# XMICRO-6502_V2_3.net
KiCad netlist of a schematic drawn in EAGLE
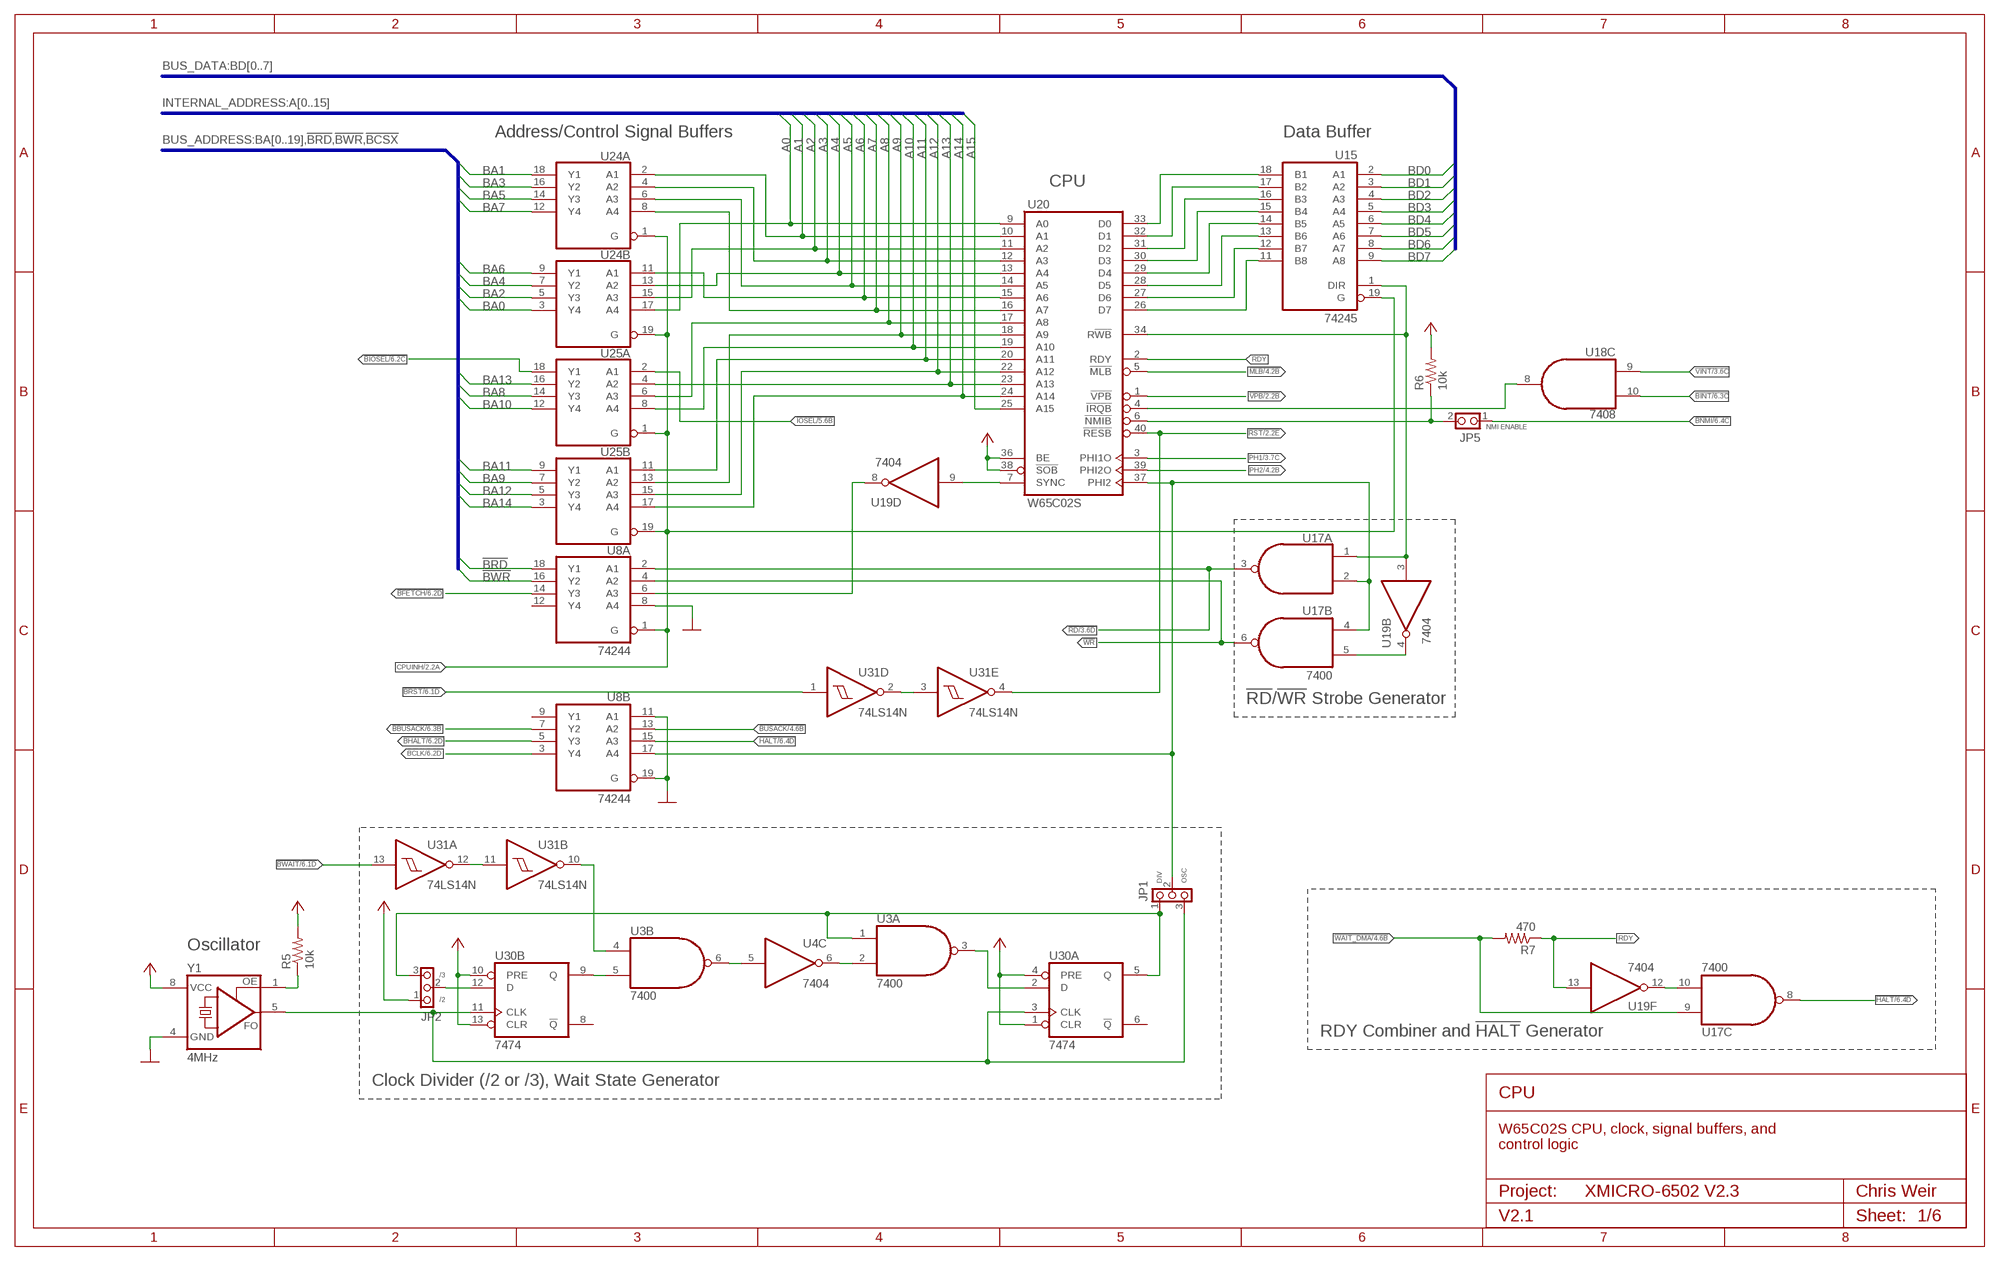
[diagram p0: schematic, sheet 1]
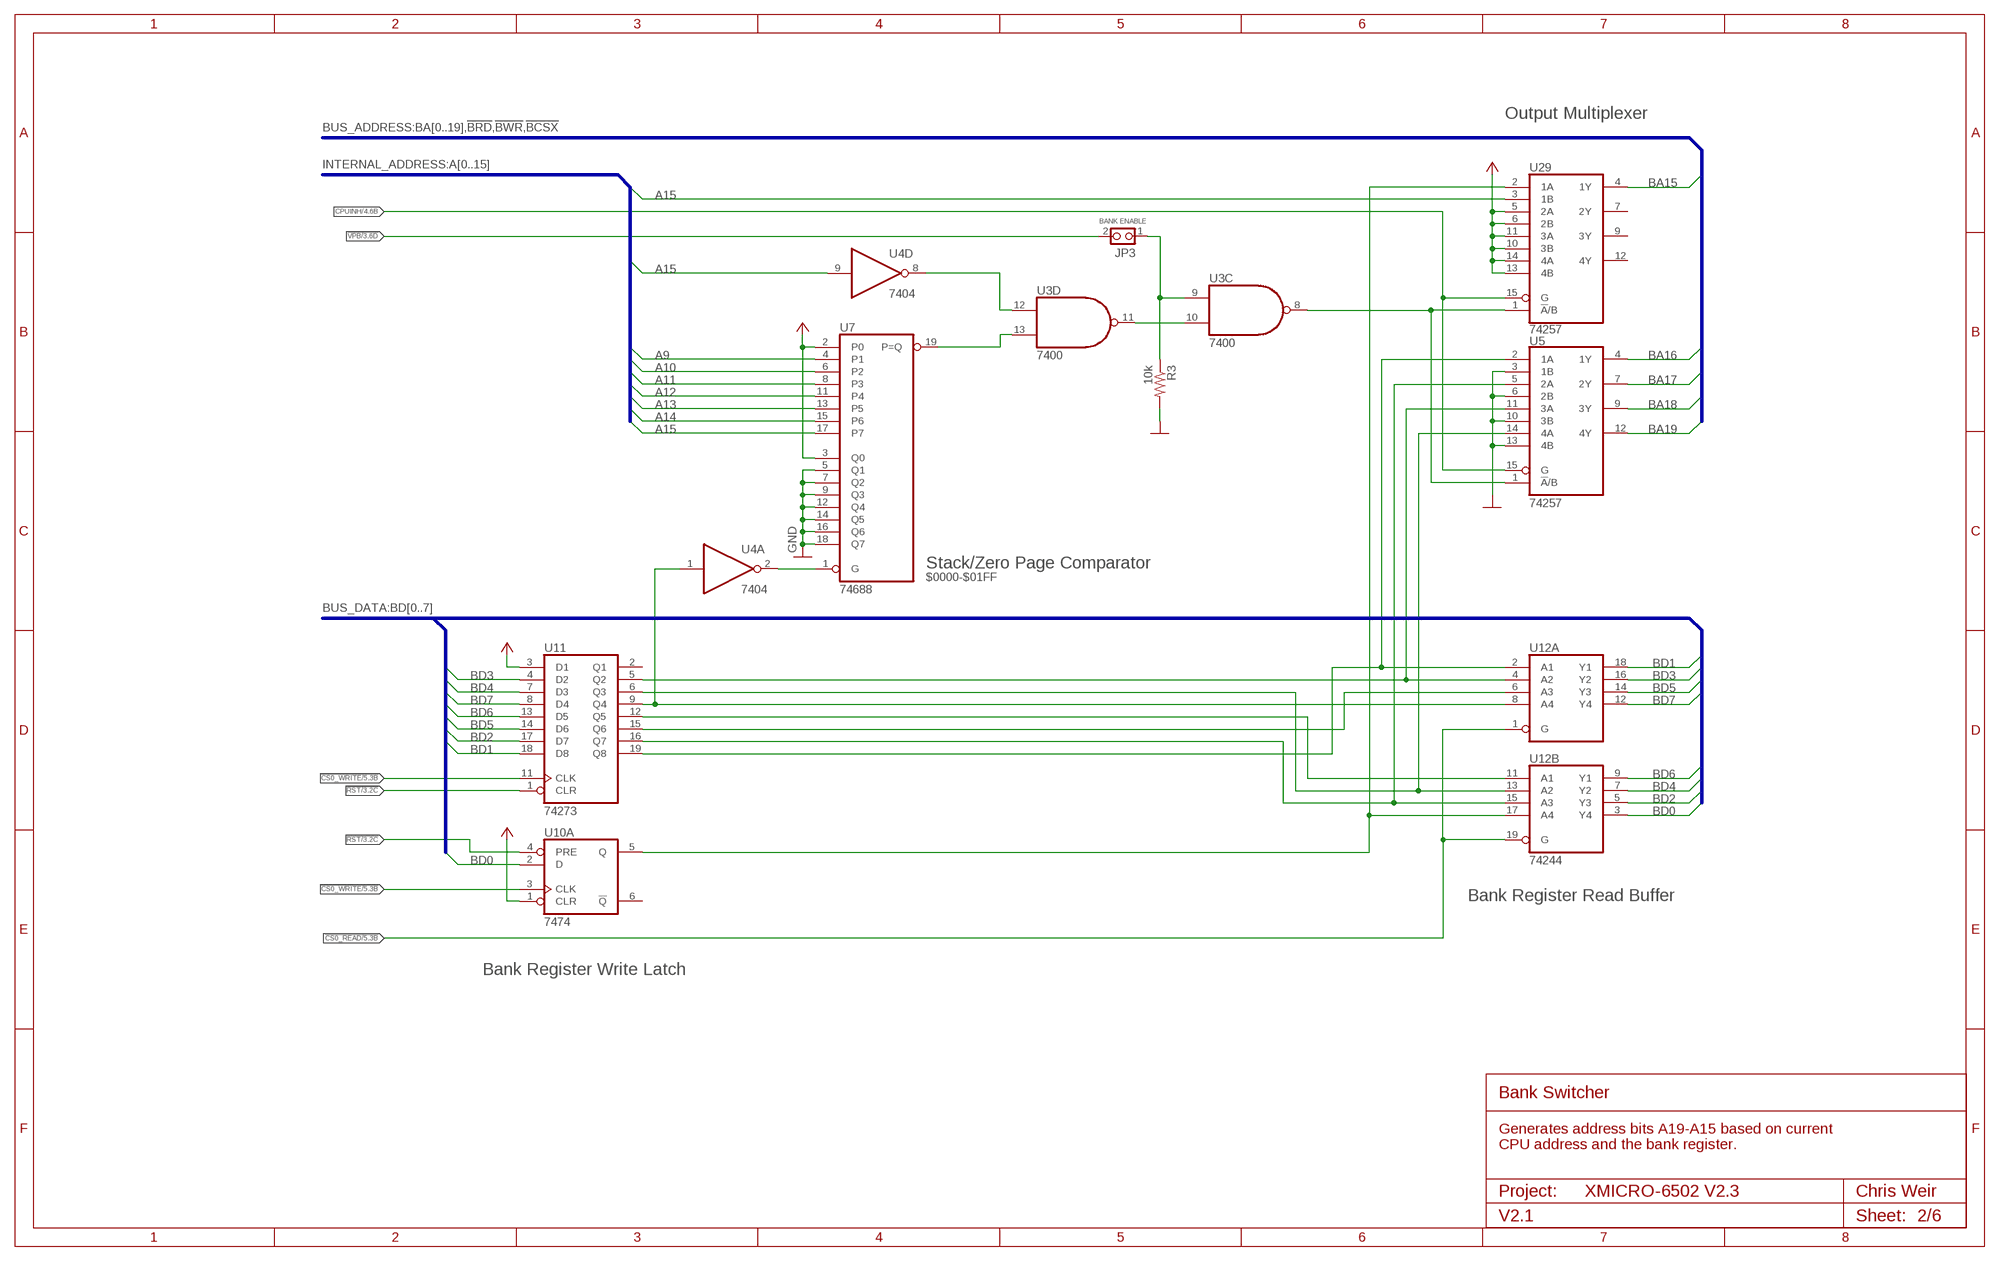
[diagram p1: schematic, sheet 2]
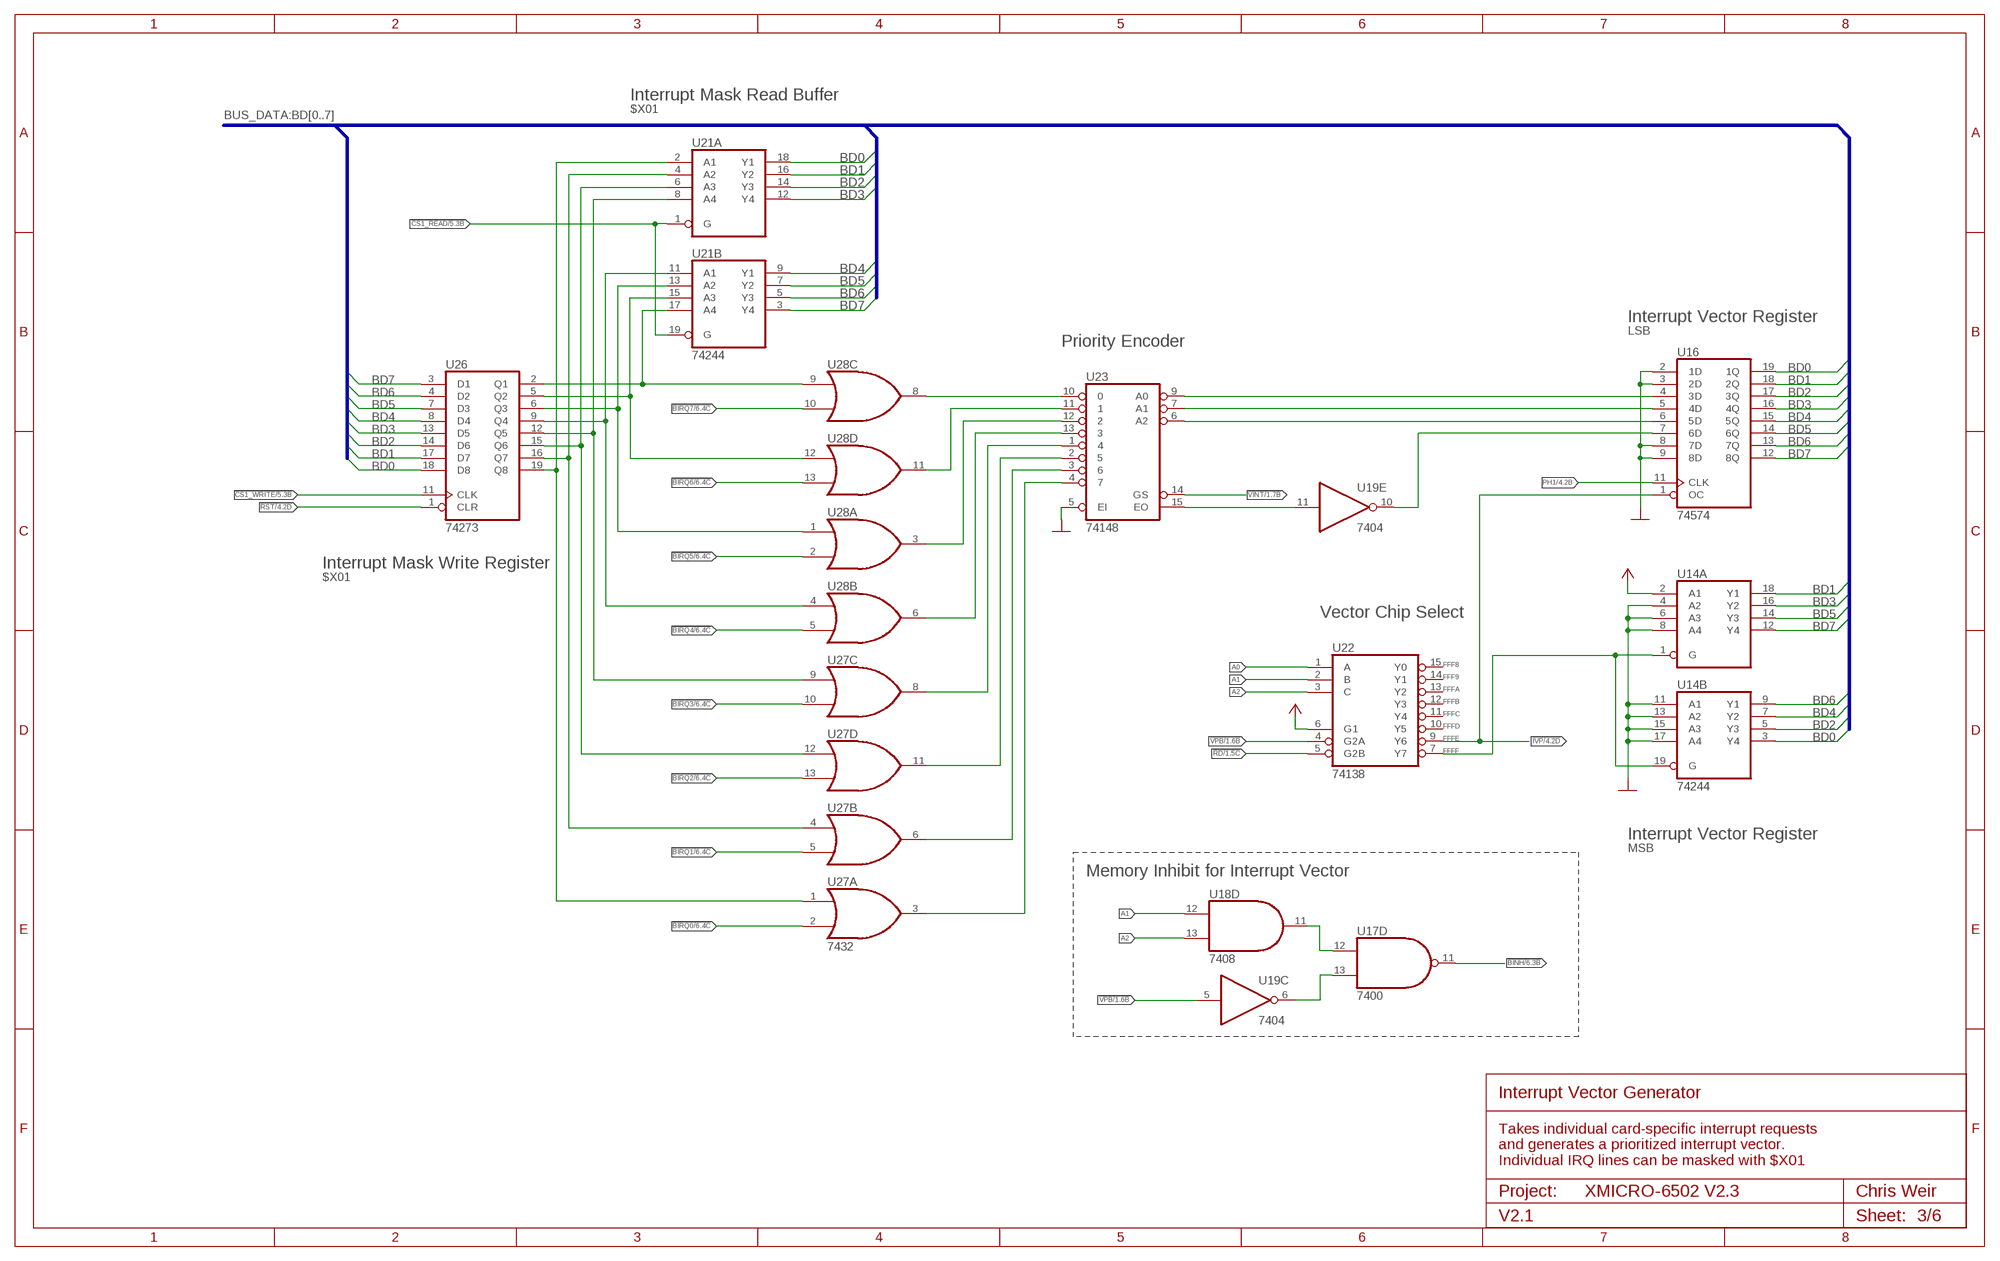
[diagram p2: schematic, sheet 3]
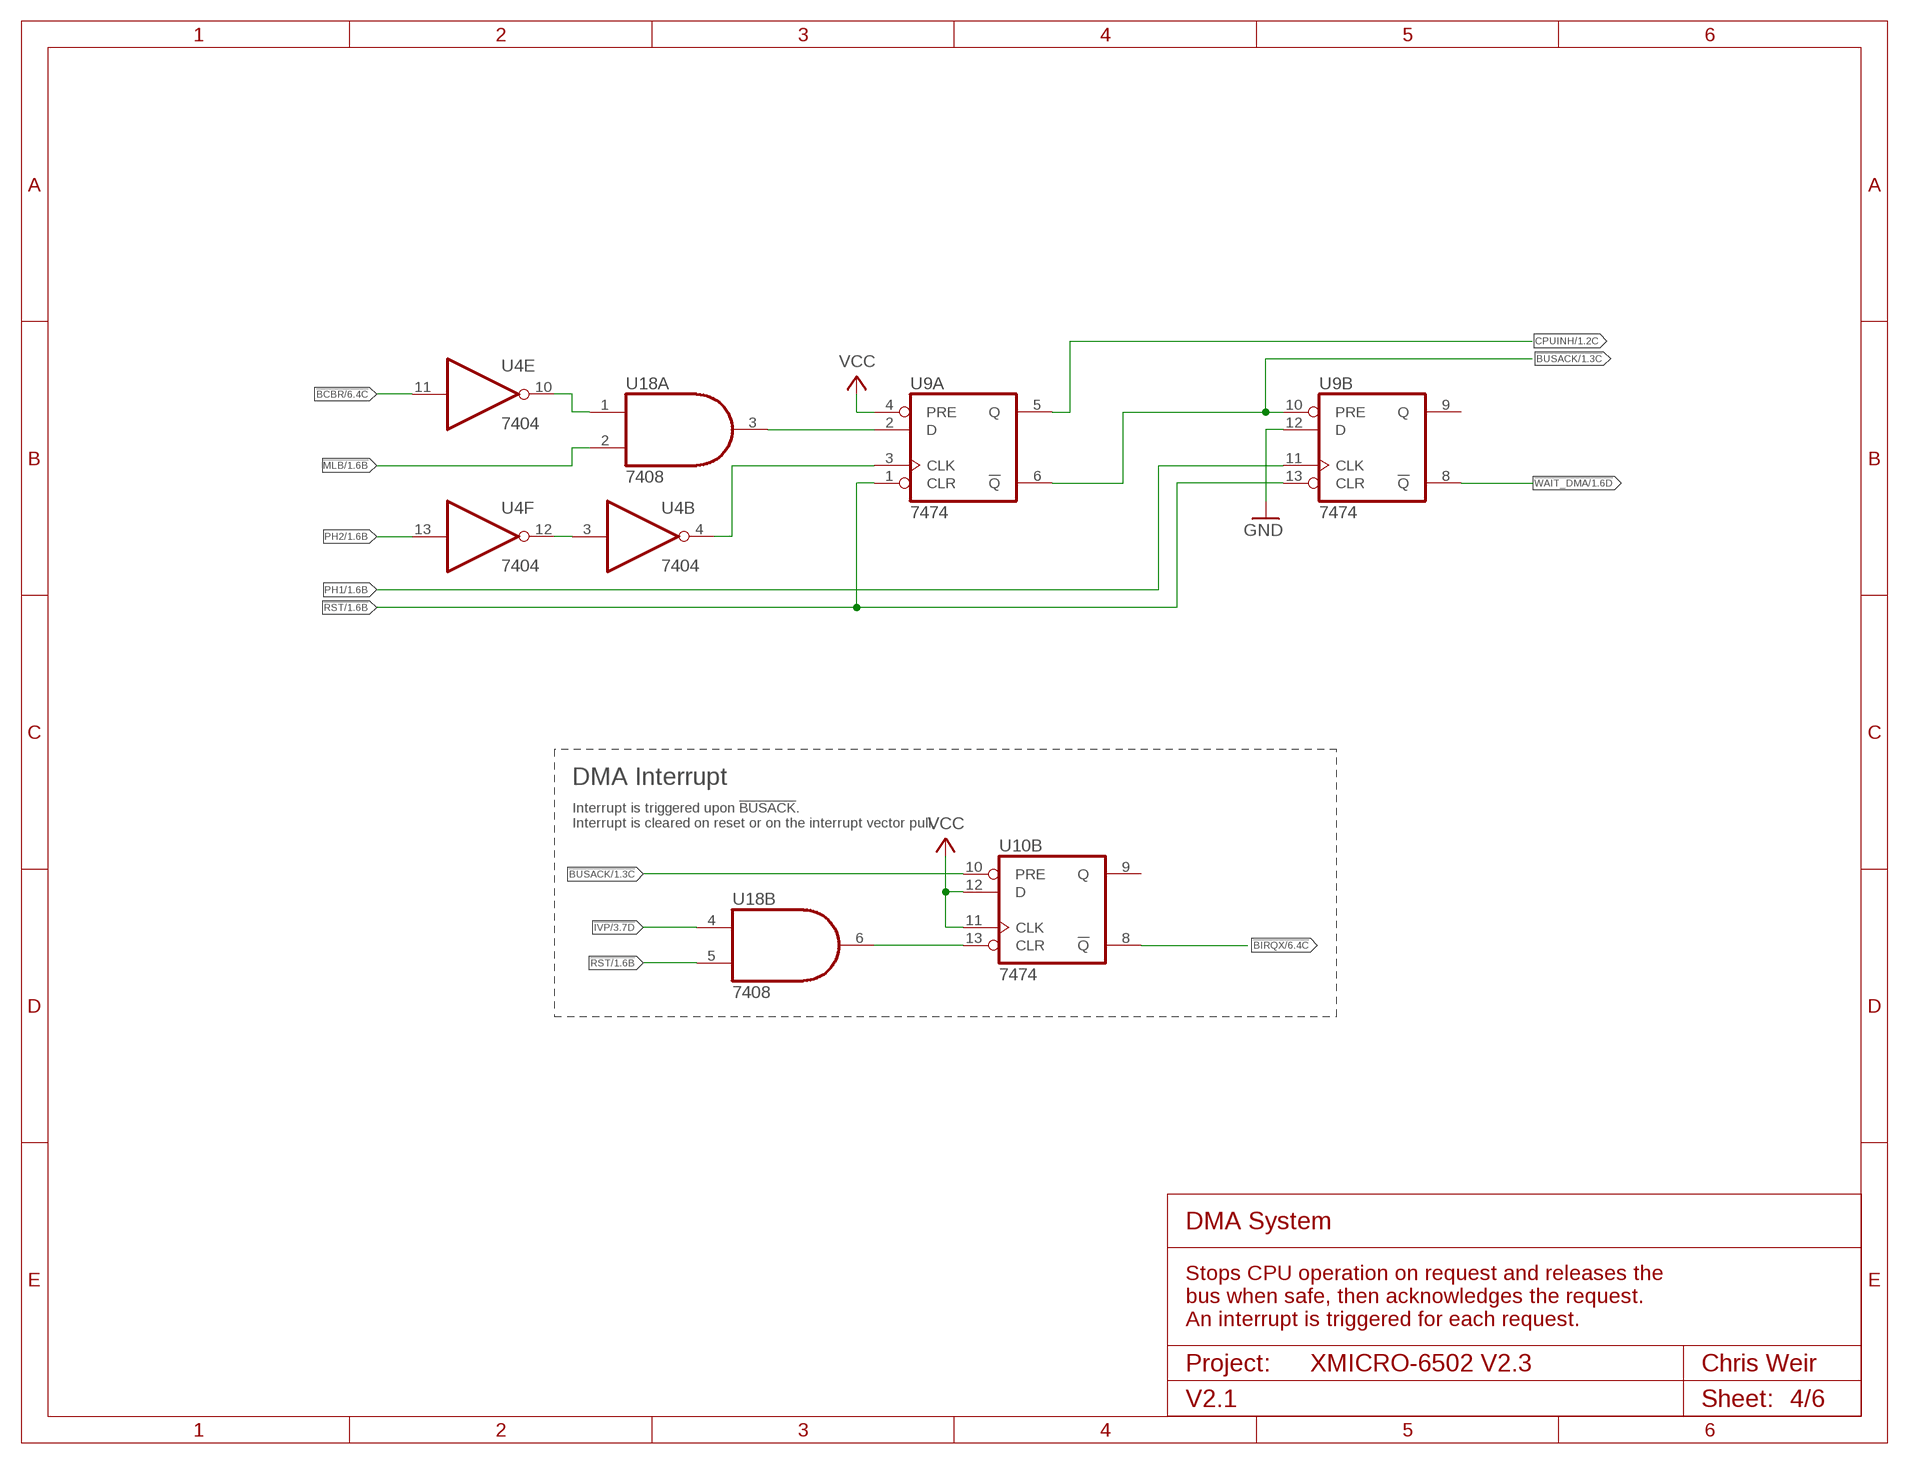
[diagram p3: schematic, sheet 4]
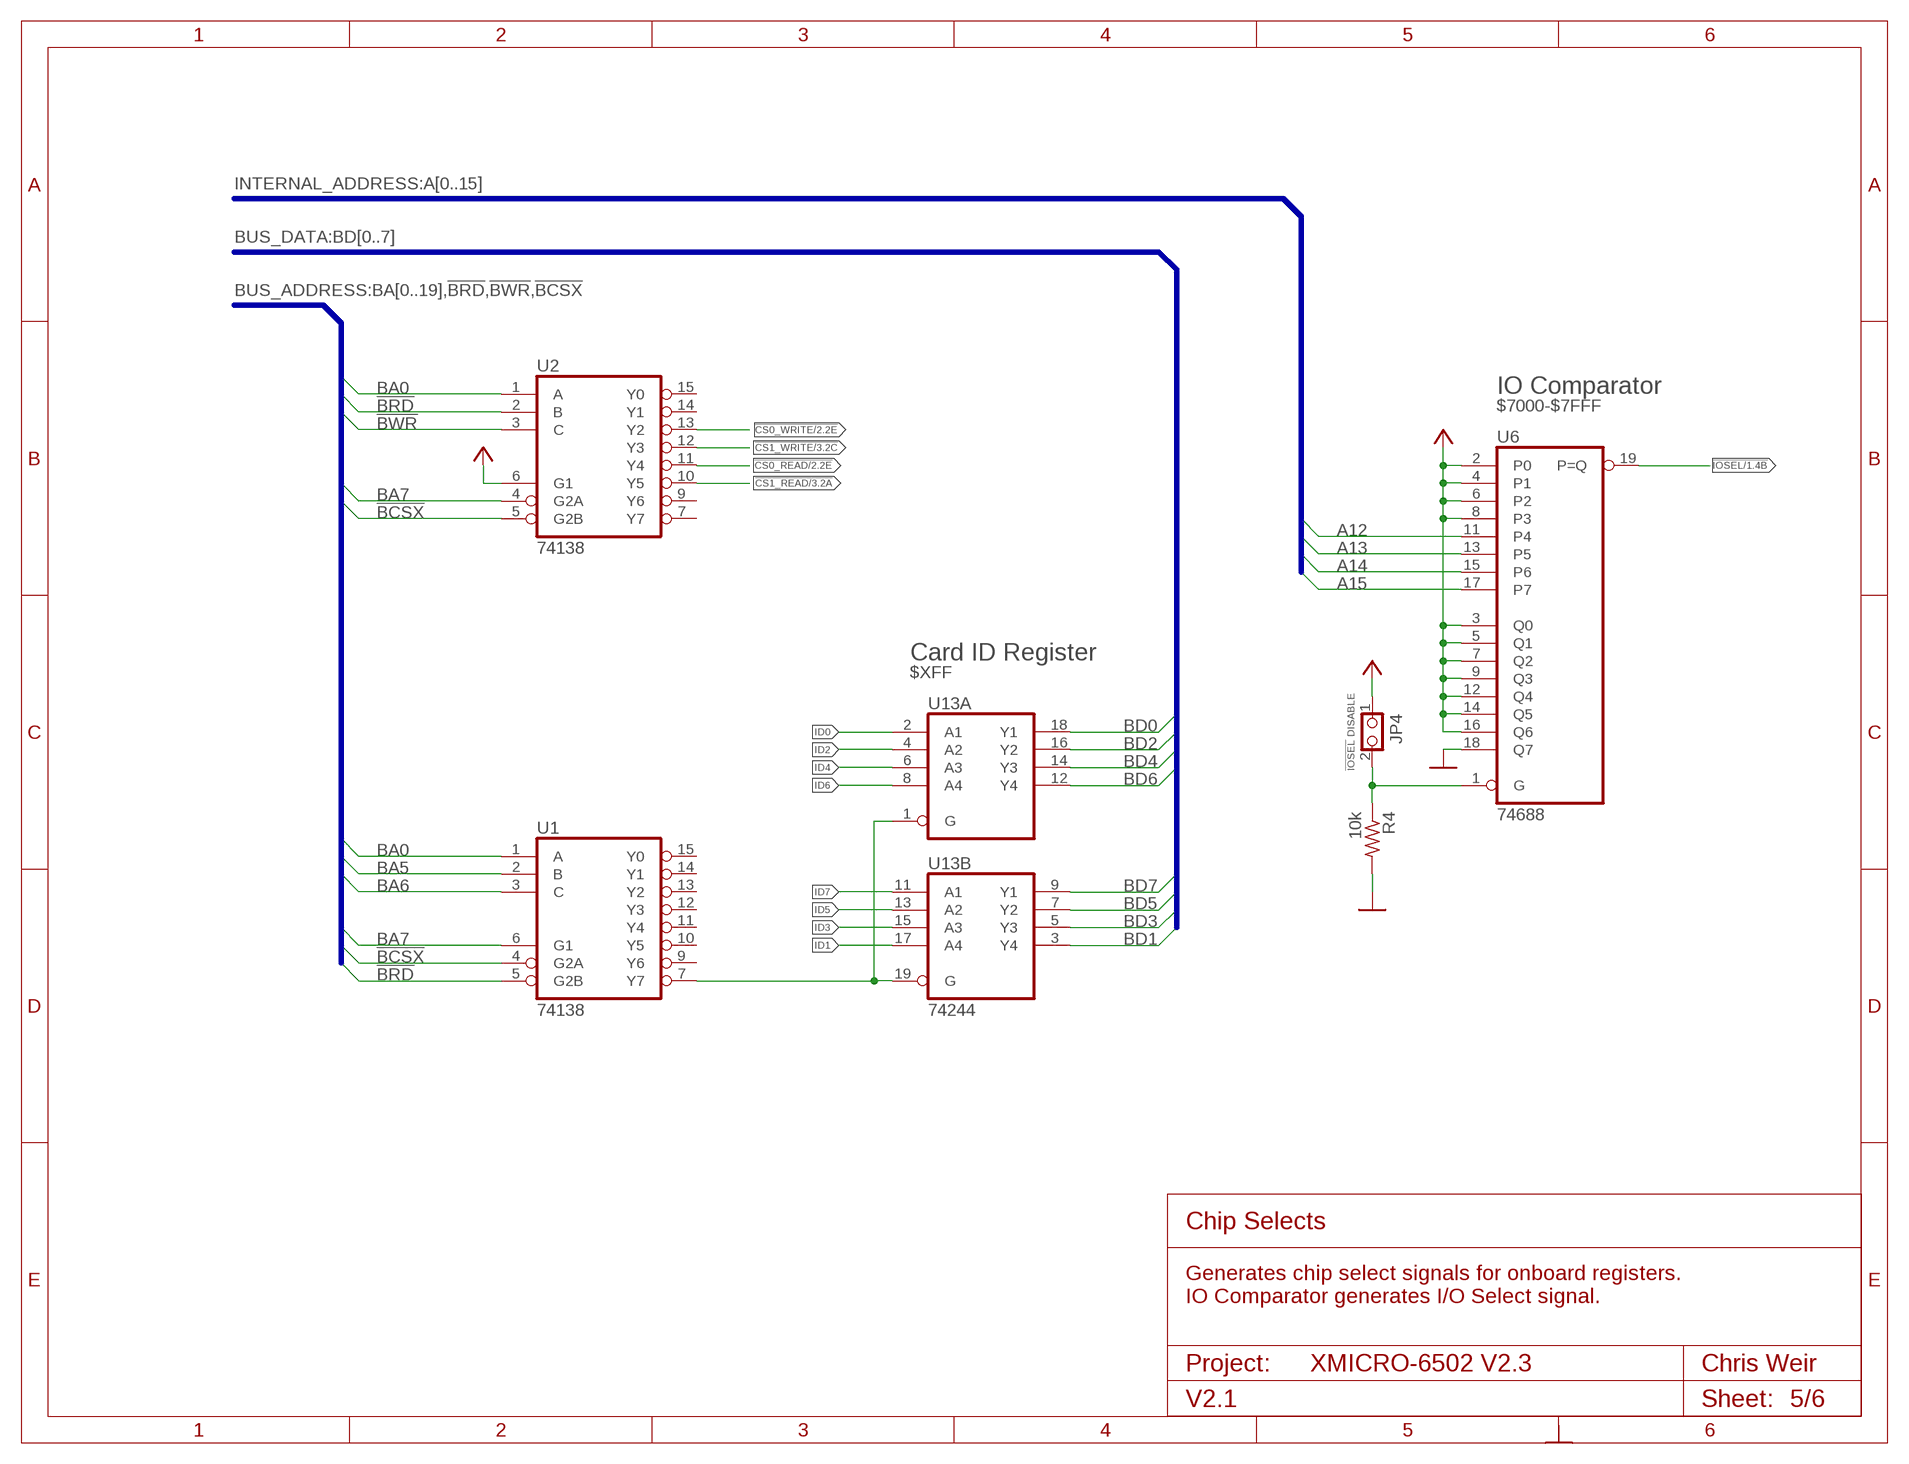
[diagram p4: schematic, sheet 5]
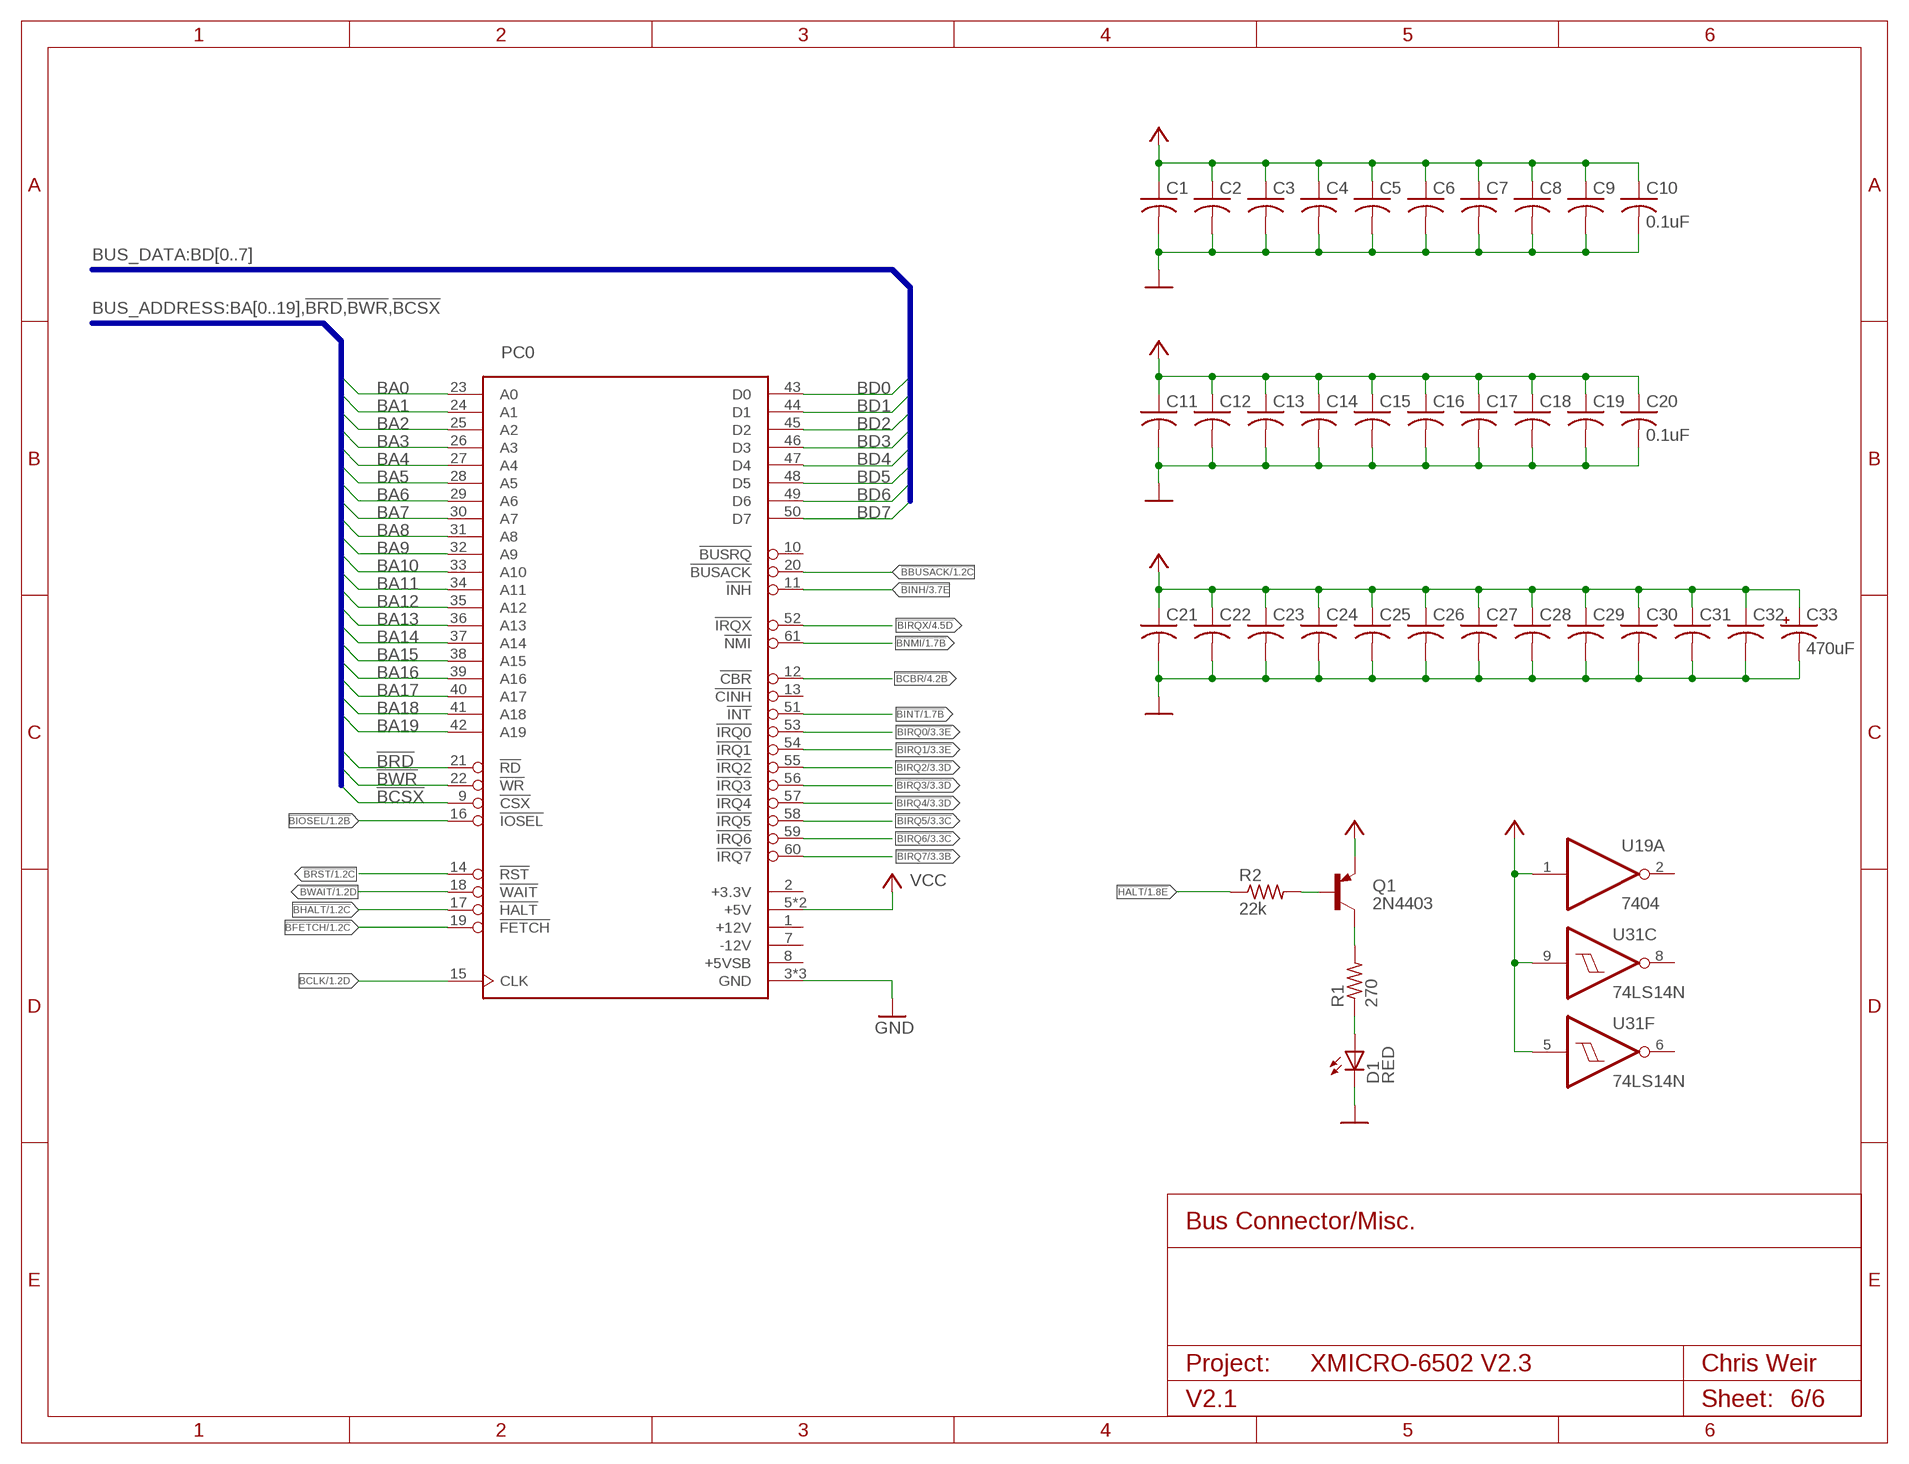
[diagram p5: schematic, sheet 6]

(export (version "E")
  (design (tool "Eeschema 10.0.6"))
  (components
    (comp (ref "C1")
      (value "0.1uF")
      (footprint "eagle-import:C025-024X044")
      (libsource (lib "eagle-import") (part "C-US025-024X044"))
    )
    (comp (ref "C2")
      (value "0.1uF")
      (footprint "eagle-import:C025-024X044")
      (libsource (lib "eagle-import") (part "C-US025-024X044"))
    )
    (comp (ref "C3")
      (value "0.1uF")
      (footprint "eagle-import:C025-024X044")
      (libsource (lib "eagle-import") (part "C-US025-024X044"))
    )
    (comp (ref "C4")
      (value "0.1uF")
      (footprint "eagle-import:C025-024X044")
      (libsource (lib "eagle-import") (part "C-US025-024X044"))
    )
    (comp (ref "C5")
      (value "0.1uF")
      (footprint "eagle-import:C025-024X044")
      (libsource (lib "eagle-import") (part "C-US025-024X044"))
    )
    (comp (ref "C6")
      (value "0.1uF")
      (footprint "eagle-import:C025-024X044")
      (libsource (lib "eagle-import") (part "C-US025-024X044"))
    )
    (comp (ref "C7")
      (value "0.1uF")
      (footprint "eagle-import:C025-024X044")
      (libsource (lib "eagle-import") (part "C-US025-024X044"))
    )
    (comp (ref "C8")
      (value "0.1uF")
      (footprint "eagle-import:C025-024X044")
      (libsource (lib "eagle-import") (part "C-US025-024X044"))
    )
    (comp (ref "C9")
      (value "0.1uF")
      (footprint "eagle-import:C025-024X044")
      (libsource (lib "eagle-import") (part "C-US025-024X044"))
    )
    (comp (ref "C10")
      (value "0.1uF")
      (footprint "eagle-import:C025-024X044")
      (libsource (lib "eagle-import") (part "C-US025-024X044"))
    )
    (comp (ref "C11")
      (value "0.1uF")
      (footprint "eagle-import:C025-024X044")
      (libsource (lib "eagle-import") (part "C-US025-024X044"))
    )
    (comp (ref "C12")
      (value "0.1uF")
      (footprint "eagle-import:C025-024X044")
      (libsource (lib "eagle-import") (part "C-US025-024X044"))
    )
    (comp (ref "C13")
      (value "0.1uF")
      (footprint "eagle-import:C025-024X044")
      (libsource (lib "eagle-import") (part "C-US025-024X044"))
    )
    (comp (ref "C14")
      (value "0.1uF")
      (footprint "eagle-import:C025-024X044")
      (libsource (lib "eagle-import") (part "C-US025-024X044"))
    )
    (comp (ref "C15")
      (value "0.1uF")
      (footprint "eagle-import:C025-024X044")
      (libsource (lib "eagle-import") (part "C-US025-024X044"))
    )
    (comp (ref "C16")
      (value "0.1uF")
      (footprint "eagle-import:C025-024X044")
      (libsource (lib "eagle-import") (part "C-US025-024X044"))
    )
    (comp (ref "C17")
      (value "0.1uF")
      (footprint "eagle-import:C025-024X044")
      (libsource (lib "eagle-import") (part "C-US025-024X044"))
    )
    (comp (ref "C18")
      (value "0.1uF")
      (footprint "eagle-import:C025-024X044")
      (libsource (lib "eagle-import") (part "C-US025-024X044"))
    )
    (comp (ref "C19")
      (value "0.1uF")
      (footprint "eagle-import:C025-024X044")
      (libsource (lib "eagle-import") (part "C-US025-024X044"))
    )
    (comp (ref "C20")
      (value "0.1uF")
      (footprint "eagle-import:C025-024X044")
      (libsource (lib "eagle-import") (part "C-US025-024X044"))
    )
    (comp (ref "C21")
      (value "0.1uF")
      (footprint "eagle-import:C025-024X044")
      (libsource (lib "eagle-import") (part "C-US025-024X044"))
    )
    (comp (ref "C22")
      (value "0.1uF")
      (footprint "eagle-import:C025-024X044")
      (libsource (lib "eagle-import") (part "C-US025-024X044"))
    )
    (comp (ref "C23")
      (value "0.1uF")
      (footprint "eagle-import:C025-024X044")
      (libsource (lib "eagle-import") (part "C-US025-024X044"))
    )
    (comp (ref "C24")
      (value "0.1uF")
      (footprint "eagle-import:C025-024X044")
      (libsource (lib "eagle-import") (part "C-US025-024X044"))
    )
    (comp (ref "C25")
      (value "0.1uF")
      (footprint "eagle-import:C025-024X044")
      (libsource (lib "eagle-import") (part "C-US025-024X044"))
    )
    (comp (ref "C26")
      (value "0.1uF")
      (footprint "eagle-import:C025-024X044")
      (libsource (lib "eagle-import") (part "C-US025-024X044"))
    )
    (comp (ref "C27")
      (value "0.1uF")
      (footprint "eagle-import:C025-024X044")
      (libsource (lib "eagle-import") (part "C-US025-024X044"))
    )
    (comp (ref "C28")
      (value "0.1uF")
      (footprint "eagle-import:C025-024X044")
      (libsource (lib "eagle-import") (part "C-US025-024X044"))
    )
    (comp (ref "C29")
      (value "0.1uF")
      (footprint "eagle-import:C025-024X044")
      (libsource (lib "eagle-import") (part "C-US025-024X044"))
    )
    (comp (ref "C30")
      (value "0.1uF")
      (footprint "eagle-import:C025-024X044")
      (libsource (lib "eagle-import") (part "C-US025-024X044"))
    )
    (comp (ref "C31")
      (value "0.1uF")
      (footprint "eagle-import:C025-024X044")
      (libsource (lib "eagle-import") (part "C-US025-024X044"))
    )
    (comp (ref "C32")
      (value "0.1uF")
      (footprint "eagle-import:C025-024X044")
      (libsource (lib "eagle-import") (part "C-US025-024X044"))
    )
    (comp (ref "C33")
      (value "470uF")
      (footprint "eagle-import:C-10-5")
      (libsource (lib "eagle-import") (part "CPOL-US-10-5"))
    )
    (comp (ref "D1")
      (value "RED")
      (footprint "eagle-import:LED5MM")
      (libsource (lib "eagle-import") (part "LED5MM"))
    )
    (comp (ref "PC0")
      (value "XMICRO-BUS-EDGE62M")
      (footprint "eagle-import:EDGE62M")
      (libsource (lib "eagle-import") (part "XMICRO-BUS-EDGE62M"))
    )
    (comp (ref "Q1")
      (value "2N4403")
      (footprint "eagle-import:TO92")
      (libsource (lib "eagle-import") (part "TRANSISTOR-PNP-2N4403"))
    )
    (comp (ref "R1")
      (value "270")
      (footprint "eagle-import:0207_10")
      (libsource (lib "eagle-import") (part "R-US_0207/10"))
    )
    (comp (ref "R2")
      (value "22k")
      (footprint "eagle-import:0207_10")
      (libsource (lib "eagle-import") (part "R-US_0207/10"))
    )
    (comp (ref "U19")
      (value "7404")
      (footprint "eagle-import:DIL14")
      (libsource (lib "eagle-import") (part "7404NLS"))
    )
    (comp (ref "U31")
      (value "74LS14N")
      (footprint "eagle-import:DIL14")
      (libsource (lib "eagle-import") (part "7414NLS"))
    )
    (comp (ref "JP1")
      (value "PINHD1X3THRU")
      (footprint "eagle-import:1X03")
      (libsource (lib "eagle-import") (part "PINHD1X3THRU"))
    )
    (comp (ref "JP2")
      (value "PINHD1X3THRU")
      (footprint "eagle-import:1X03")
      (libsource (lib "eagle-import") (part "PINHD1X3THRU"))
    )
    (comp (ref "JP5")
      (value "PINHD-1X2THRU")
      (footprint "eagle-import:1X02")
      (libsource (lib "eagle-import") (part "PINHD-1X2THRU"))
    )
    (comp (ref "R5")
      (value "10k")
      (footprint "eagle-import:0207_10")
      (libsource (lib "eagle-import") (part "R-US_0207/10"))
    )
    (comp (ref "R6")
      (value "10k")
      (footprint "eagle-import:0207_10")
      (libsource (lib "eagle-import") (part "R-US_0207/10"))
    )
    (comp (ref "R7")
      (value "470")
      (footprint "eagle-import:0207_10")
      (libsource (lib "eagle-import") (part "R-US_0207/10"))
    )
    (comp (ref "U3")
      (value "7400")
      (footprint "eagle-import:DIL14")
      (libsource (lib "eagle-import") (part "7400NLS"))
    )
    (comp (ref "U4")
      (value "7404")
      (footprint "eagle-import:DIL14")
      (libsource (lib "eagle-import") (part "7404NLS"))
    )
    (comp (ref "U8")
      (value "74244")
      (footprint "eagle-import:DIL20")
      (libsource (lib "eagle-import") (part "74244NLS"))
    )
    (comp (ref "U15")
      (value "74245")
      (footprint "eagle-import:DIL20")
      (libsource (lib "eagle-import") (part "74245NLS"))
    )
    (comp (ref "U17")
      (value "7400")
      (footprint "eagle-import:DIL14")
      (libsource (lib "eagle-import") (part "7400NLS"))
    )
    (comp (ref "U18")
      (value "7408")
      (footprint "eagle-import:DIL14")
      (libsource (lib "eagle-import") (part "7408NLS"))
    )
    (comp (ref "U20")
      (value "W65C02S")
      (footprint "eagle-import:DIL40")
      (libsource (lib "eagle-import") (part "W65C02P"))
    )
    (comp (ref "U24")
      (value "74244")
      (footprint "eagle-import:DIL20")
      (libsource (lib "eagle-import") (part "74244NLS"))
    )
    (comp (ref "U25")
      (value "74244")
      (footprint "eagle-import:DIL20")
      (libsource (lib "eagle-import") (part "74244NLS"))
    )
    (comp (ref "U30")
      (value "7474")
      (footprint "eagle-import:DIL14")
      (libsource (lib "eagle-import") (part "7474NLS"))
    )
    (comp (ref "Y1")
      (value "4MHz")
      (footprint "eagle-import:DIL08S")
      (libsource (lib "eagle-import") (part "OSC-OE"))
    )
    (comp (ref "JP3")
      (value "PINHD-1X2THRU")
      (footprint "eagle-import:1X02")
      (libsource (lib "eagle-import") (part "PINHD-1X2THRU"))
    )
    (comp (ref "R3")
      (value "10k")
      (footprint "eagle-import:0207_10")
      (libsource (lib "eagle-import") (part "R-US_0207/10"))
    )
    (comp (ref "U5")
      (value "74257")
      (footprint "eagle-import:DIL16")
      (libsource (lib "eagle-import") (part "74257NLS"))
    )
    (comp (ref "U7")
      (value "74688")
      (footprint "eagle-import:DIL20")
      (libsource (lib "eagle-import") (part "74688NLS"))
    )
    (comp (ref "U10")
      (value "7474")
      (footprint "eagle-import:DIL14")
      (libsource (lib "eagle-import") (part "7474NLS"))
    )
    (comp (ref "U11")
      (value "74273")
      (footprint "eagle-import:DIL20")
      (libsource (lib "eagle-import") (part "74273N"))
    )
    (comp (ref "U12")
      (value "74244")
      (footprint "eagle-import:DIL20")
      (libsource (lib "eagle-import") (part "74244NLS"))
    )
    (comp (ref "U29")
      (value "74257")
      (footprint "eagle-import:DIL16")
      (libsource (lib "eagle-import") (part "74257NLS"))
    )
    (comp (ref "U9")
      (value "7474")
      (footprint "eagle-import:DIL14")
      (libsource (lib "eagle-import") (part "7474NLS"))
    )
    (comp (ref "U14")
      (value "74244")
      (footprint "eagle-import:DIL20")
      (libsource (lib "eagle-import") (part "74244NLS"))
    )
    (comp (ref "U16")
      (value "74574")
      (footprint "eagle-import:DIL20")
      (libsource (lib "eagle-import") (part "74574NHC"))
    )
    (comp (ref "U21")
      (value "74244")
      (footprint "eagle-import:DIL20")
      (libsource (lib "eagle-import") (part "74244NLS"))
    )
    (comp (ref "U22")
      (value "74138")
      (footprint "eagle-import:DIL16")
      (libsource (lib "eagle-import") (part "74138NLS"))
    )
    (comp (ref "U23")
      (value "74148")
      (footprint "eagle-import:DIL16")
      (libsource (lib "eagle-import") (part "74148NLS"))
    )
    (comp (ref "U26")
      (value "74273")
      (footprint "eagle-import:DIL20")
      (libsource (lib "eagle-import") (part "74273N"))
    )
    (comp (ref "U27")
      (value "7432")
      (footprint "eagle-import:DIL14")
      (libsource (lib "eagle-import") (part "7432NLS"))
    )
    (comp (ref "U28")
      (value "7432")
      (footprint "eagle-import:DIL14")
      (libsource (lib "eagle-import") (part "7432NLS"))
    )
    (comp (ref "JP4")
      (value "PINHD-1X2THRU")
      (footprint "eagle-import:1X02")
      (libsource (lib "eagle-import") (part "PINHD-1X2THRU"))
    )
    (comp (ref "R4")
      (value "10k")
      (footprint "eagle-import:0207_10")
      (libsource (lib "eagle-import") (part "R-US_0207/10"))
    )
    (comp (ref "U1")
      (value "74138")
      (footprint "eagle-import:DIL16")
      (libsource (lib "eagle-import") (part "74138NLS"))
    )
    (comp (ref "U2")
      (value "74138")
      (footprint "eagle-import:DIL16")
      (libsource (lib "eagle-import") (part "74138NLS"))
    )
    (comp (ref "U6")
      (value "74688")
      (footprint "eagle-import:DIL20")
      (libsource (lib "eagle-import") (part "74688NLS"))
    )
    (comp (ref "U13")
      (value "74244")
      (footprint "eagle-import:DIL20")
      (libsource (lib "eagle-import") (part "74244NLS"))
    )
  )
  (nets
    (net (code "105") (name "A0") (class "Default")
      (node (ref "U20") (pin "9") (pinfunction "A0_9") (pintype "output"))
      (node (ref "U22") (pin "1") (pinfunction "A_1") (pintype "input"))
      (node (ref "U24") (pin "17") (pinfunction "A4_17") (pintype "input"))
    )
    (net (code "106") (name "A1") (class "Default")
      (node (ref "U18") (pin "12") (pinfunction "I0_12") (pintype "input"))
      (node (ref "U20") (pin "10") (pinfunction "A1_10") (pintype "output"))
      (node (ref "U22") (pin "2") (pinfunction "B_2") (pintype "input"))
      (node (ref "U24") (pin "2") (pinfunction "A1_2") (pintype "input"))
    )
    (net (code "107") (name "A2") (class "Default")
      (node (ref "U18") (pin "13") (pinfunction "I1_13") (pintype "input"))
      (node (ref "U20") (pin "11") (pinfunction "A2_11") (pintype "output"))
      (node (ref "U22") (pin "3") (pinfunction "C_3") (pintype "input"))
      (node (ref "U24") (pin "15") (pinfunction "A3_15") (pintype "input"))
    )
    (net (code "108") (name "A3") (class "Default")
      (node (ref "U20") (pin "12") (pinfunction "A3_12") (pintype "output"))
      (node (ref "U24") (pin "4") (pinfunction "A2_4") (pintype "input"))
    )
    (net (code "109") (name "A4") (class "Default")
      (node (ref "U20") (pin "13") (pinfunction "A4_13") (pintype "output"))
      (node (ref "U24") (pin "13") (pinfunction "A2_13") (pintype "input"))
    )
    (net (code "110") (name "A5") (class "Default")
      (node (ref "U20") (pin "14") (pinfunction "A5_14") (pintype "output"))
      (node (ref "U24") (pin "6") (pinfunction "A3_6") (pintype "input"))
    )
    (net (code "111") (name "A6") (class "Default")
      (node (ref "U20") (pin "15") (pinfunction "A6_15") (pintype "output"))
      (node (ref "U24") (pin "11") (pinfunction "A1_11") (pintype "input"))
    )
    (net (code "112") (name "A7") (class "Default")
      (node (ref "U20") (pin "16") (pinfunction "A7_16") (pintype "output"))
      (node (ref "U24") (pin "8") (pinfunction "A4_8") (pintype "input"))
    )
    (net (code "113") (name "A8") (class "Default")
      (node (ref "U20") (pin "17") (pinfunction "A8_17") (pintype "output"))
      (node (ref "U25") (pin "6") (pinfunction "A3_6") (pintype "input"))
    )
    (net (code "114") (name "A9") (class "Default")
      (node (ref "U20") (pin "18") (pinfunction "A9_18") (pintype "output"))
      (node (ref "U25") (pin "13") (pinfunction "A2_13") (pintype "input"))
      (node (ref "U7") (pin "4") (pinfunction "P1_4") (pintype "input"))
    )
    (net (code "115") (name "A10") (class "Default")
      (node (ref "U20") (pin "19") (pinfunction "A10_19") (pintype "output"))
      (node (ref "U25") (pin "8") (pinfunction "A4_8") (pintype "input"))
      (node (ref "U7") (pin "6") (pinfunction "P2_6") (pintype "input"))
    )
    (net (code "116") (name "A11") (class "Default")
      (node (ref "U20") (pin "20") (pinfunction "A11_20") (pintype "output"))
      (node (ref "U25") (pin "11") (pinfunction "A1_11") (pintype "input"))
      (node (ref "U7") (pin "8") (pinfunction "P3_8") (pintype "input"))
    )
    (net (code "117") (name "A12") (class "Default")
      (node (ref "U20") (pin "22") (pinfunction "A12_22") (pintype "output"))
      (node (ref "U25") (pin "15") (pinfunction "A3_15") (pintype "input"))
      (node (ref "U6") (pin "11") (pinfunction "P4_11") (pintype "input"))
      (node (ref "U7") (pin "11") (pinfunction "P4_11") (pintype "input"))
    )
    (net (code "118") (name "A13") (class "Default")
      (node (ref "U20") (pin "23") (pinfunction "A13_23") (pintype "output"))
      (node (ref "U25") (pin "4") (pinfunction "A2_4") (pintype "input"))
      (node (ref "U6") (pin "13") (pinfunction "P5_13") (pintype "input"))
      (node (ref "U7") (pin "13") (pinfunction "P5_13") (pintype "input"))
    )
    (net (code "119") (name "A14") (class "Default")
      (node (ref "U20") (pin "24") (pinfunction "A14_24") (pintype "output"))
      (node (ref "U25") (pin "17") (pinfunction "A4_17") (pintype "input"))
      (node (ref "U6") (pin "15") (pinfunction "P6_15") (pintype "input"))
      (node (ref "U7") (pin "15") (pinfunction "P6_15") (pintype "input"))
    )
    (net (code "120") (name "A15") (class "Default")
      (node (ref "U20") (pin "25") (pinfunction "A15_25") (pintype "output"))
      (node (ref "U29") (pin "3") (pinfunction "1B_3") (pintype "input"))
      (node (ref "U4") (pin "9") (pinfunction "I_9") (pintype "input"))
      (node (ref "U6") (pin "17") (pinfunction "P7_17") (pintype "input"))
      (node (ref "U7") (pin "17") (pinfunction "P7_17") (pintype "input"))
    )
    (net (code "121") (name "BA0") (class "Default")
      (node (ref "PC0") (pin "23") (pinfunction "A0_23") (pintype "bidirectional"))
      (node (ref "U1") (pin "1") (pinfunction "A_1") (pintype "input"))
      (node (ref "U2") (pin "1") (pinfunction "A_1") (pintype "input"))
      (node (ref "U24") (pin "3") (pinfunction "Y4_3") (pintype "tri_state"))
    )
    (net (code "122") (name "BA1") (class "Default")
      (node (ref "PC0") (pin "24") (pinfunction "A1_24") (pintype "bidirectional"))
      (node (ref "U24") (pin "18") (pinfunction "Y1_18") (pintype "tri_state"))
    )
    (net (code "123") (name "BA2") (class "Default")
      (node (ref "PC0") (pin "25") (pinfunction "A2_25") (pintype "bidirectional"))
      (node (ref "U24") (pin "5") (pinfunction "Y3_5") (pintype "tri_state"))
    )
    (net (code "124") (name "BA3") (class "Default")
      (node (ref "PC0") (pin "26") (pinfunction "A3_26") (pintype "bidirectional"))
      (node (ref "U24") (pin "16") (pinfunction "Y2_16") (pintype "tri_state"))
    )
    (net (code "125") (name "BA4") (class "Default")
      (node (ref "PC0") (pin "27") (pinfunction "A4_27") (pintype "bidirectional"))
      (node (ref "U24") (pin "7") (pinfunction "Y2_7") (pintype "tri_state"))
    )
    (net (code "126") (name "BA5") (class "Default")
      (node (ref "PC0") (pin "28") (pinfunction "A5_28") (pintype "bidirectional"))
      (node (ref "U1") (pin "2") (pinfunction "B_2") (pintype "input"))
      (node (ref "U24") (pin "14") (pinfunction "Y3_14") (pintype "tri_state"))
    )
    (net (code "127") (name "BA6") (class "Default")
      (node (ref "PC0") (pin "29") (pinfunction "A6_29") (pintype "bidirectional"))
      (node (ref "U1") (pin "3") (pinfunction "C_3") (pintype "input"))
      (node (ref "U24") (pin "9") (pinfunction "Y1_9") (pintype "tri_state"))
    )
    (net (code "128") (name "BA7") (class "Default")
      (node (ref "PC0") (pin "30") (pinfunction "A7_30") (pintype "bidirectional"))
      (node (ref "U1") (pin "6") (pinfunction "G1_6") (pintype "input"))
      (node (ref "U2") (pin "4") (pinfunction "G2A_4") (pintype "input"))
      (node (ref "U24") (pin "12") (pinfunction "Y4_12") (pintype "tri_state"))
    )
    (net (code "129") (name "BA8") (class "Default")
      (node (ref "PC0") (pin "31") (pinfunction "A8_31") (pintype "bidirectional"))
      (node (ref "U25") (pin "14") (pinfunction "Y3_14") (pintype "tri_state"))
    )
    (net (code "130") (name "BA9") (class "Default")
      (node (ref "PC0") (pin "32") (pinfunction "A9_32") (pintype "bidirectional"))
      (node (ref "U25") (pin "7") (pinfunction "Y2_7") (pintype "tri_state"))
    )
    (net (code "131") (name "BA10") (class "Default")
      (node (ref "PC0") (pin "33") (pinfunction "A10_33") (pintype "bidirectional"))
      (node (ref "U25") (pin "12") (pinfunction "Y4_12") (pintype "tri_state"))
    )
    (net (code "132") (name "BA11") (class "Default")
      (node (ref "PC0") (pin "34") (pinfunction "A11_34") (pintype "bidirectional"))
      (node (ref "U25") (pin "9") (pinfunction "Y1_9") (pintype "tri_state"))
    )
    (net (code "133") (name "BA12") (class "Default")
      (node (ref "PC0") (pin "35") (pinfunction "A12_35") (pintype "bidirectional"))
      (node (ref "U25") (pin "5") (pinfunction "Y3_5") (pintype "tri_state"))
    )
    (net (code "134") (name "BA13") (class "Default")
      (node (ref "PC0") (pin "36") (pinfunction "A13_36") (pintype "bidirectional"))
      (node (ref "U25") (pin "16") (pinfunction "Y2_16") (pintype "tri_state"))
    )
    (net (code "135") (name "BA14") (class "Default")
      (node (ref "PC0") (pin "37") (pinfunction "A14_37") (pintype "bidirectional"))
      (node (ref "U25") (pin "3") (pinfunction "Y4_3") (pintype "tri_state"))
    )
    (net (code "136") (name "BA15") (class "Default")
      (node (ref "PC0") (pin "38") (pinfunction "A15_38") (pintype "bidirectional"))
      (node (ref "U29") (pin "4") (pinfunction "1Y_4") (pintype "tri_state"))
    )
    (net (code "137") (name "BA16") (class "Default")
      (node (ref "PC0") (pin "39") (pinfunction "A16_39") (pintype "bidirectional"))
      (node (ref "U5") (pin "4") (pinfunction "1Y_4") (pintype "tri_state"))
    )
    (net (code "138") (name "BA17") (class "Default")
      (node (ref "PC0") (pin "40") (pinfunction "A17_40") (pintype "bidirectional"))
      (node (ref "U5") (pin "7") (pinfunction "2Y_7") (pintype "tri_state"))
    )
    (net (code "139") (name "BA18") (class "Default")
      (node (ref "PC0") (pin "41") (pinfunction "A18_41") (pintype "bidirectional"))
      (node (ref "U5") (pin "9") (pinfunction "3Y_9") (pintype "tri_state"))
    )
    (net (code "140") (name "BA19") (class "Default")
      (node (ref "PC0") (pin "42") (pinfunction "A19_42") (pintype "bidirectional"))
      (node (ref "U5") (pin "12") (pinfunction "4Y_12") (pintype "tri_state"))
    )
    (net (code "141") (name "BCLK") (class "Default")
      (node (ref "PC0") (pin "15") (pinfunction "CLK_15") (pintype "bidirectional"))
      (node (ref "U8") (pin "3") (pinfunction "Y4_3") (pintype "tri_state"))
    )
    (net (code "142") (name "BD0") (class "Default")
      (node (ref "PC0") (pin "43") (pinfunction "D0_43") (pintype "bidirectional"))
      (node (ref "U10") (pin "2") (pinfunction "D_2") (pintype "input"))
      (node (ref "U12") (pin "3") (pinfunction "Y4_3") (pintype "tri_state"))
      (node (ref "U13") (pin "18") (pinfunction "Y1_18") (pintype "tri_state"))
      (node (ref "U14") (pin "3") (pinfunction "Y4_3") (pintype "tri_state"))
      (node (ref "U15") (pin "2") (pinfunction "A1_2") (pintype "bidirectional"))
      (node (ref "U16") (pin "19") (pinfunction "1Q_19") (pintype "tri_state"))
      (node (ref "U21") (pin "18") (pinfunction "Y1_18") (pintype "tri_state"))
      (node (ref "U26") (pin "18") (pinfunction "D8_18") (pintype "input"))
    )
    (net (code "143") (name "BD1") (class "Default")
      (node (ref "PC0") (pin "44") (pinfunction "D1_44") (pintype "bidirectional"))
      (node (ref "U11") (pin "18") (pinfunction "D8_18") (pintype "input"))
      (node (ref "U12") (pin "18") (pinfunction "Y1_18") (pintype "tri_state"))
      (node (ref "U13") (pin "3") (pinfunction "Y4_3") (pintype "tri_state"))
      (node (ref "U14") (pin "18") (pinfunction "Y1_18") (pintype "tri_state"))
      (node (ref "U15") (pin "3") (pinfunction "A2_3") (pintype "bidirectional"))
      (node (ref "U16") (pin "18") (pinfunction "2Q_18") (pintype "tri_state"))
      (node (ref "U21") (pin "16") (pinfunction "Y2_16") (pintype "tri_state"))
      (node (ref "U26") (pin "17") (pinfunction "D7_17") (pintype "input"))
    )
    (net (code "144") (name "BD2") (class "Default")
      (node (ref "PC0") (pin "45") (pinfunction "D2_45") (pintype "bidirectional"))
      (node (ref "U11") (pin "17") (pinfunction "D7_17") (pintype "input"))
      (node (ref "U12") (pin "5") (pinfunction "Y3_5") (pintype "tri_state"))
      (node (ref "U13") (pin "16") (pinfunction "Y2_16") (pintype "tri_state"))
      (node (ref "U14") (pin "5") (pinfunction "Y3_5") (pintype "tri_state"))
      (node (ref "U15") (pin "4") (pinfunction "A3_4") (pintype "bidirectional"))
      (node (ref "U16") (pin "17") (pinfunction "3Q_17") (pintype "tri_state"))
      (node (ref "U21") (pin "14") (pinfunction "Y3_14") (pintype "tri_state"))
      (node (ref "U26") (pin "14") (pinfunction "D6_14") (pintype "input"))
    )
    (net (code "145") (name "BD3") (class "Default")
      (node (ref "PC0") (pin "46") (pinfunction "D3_46") (pintype "bidirectional"))
      (node (ref "U11") (pin "4") (pinfunction "D2_4") (pintype "input"))
      (node (ref "U12") (pin "16") (pinfunction "Y2_16") (pintype "tri_state"))
      (node (ref "U13") (pin "5") (pinfunction "Y3_5") (pintype "tri_state"))
      (node (ref "U14") (pin "16") (pinfunction "Y2_16") (pintype "tri_state"))
      (node (ref "U15") (pin "5") (pinfunction "A4_5") (pintype "bidirectional"))
      (node (ref "U16") (pin "16") (pinfunction "4Q_16") (pintype "tri_state"))
      (node (ref "U21") (pin "12") (pinfunction "Y4_12") (pintype "tri_state"))
      (node (ref "U26") (pin "13") (pinfunction "D5_13") (pintype "input"))
    )
    (net (code "146") (name "BD4") (class "Default")
      (node (ref "PC0") (pin "47") (pinfunction "D4_47") (pintype "bidirectional"))
      (node (ref "U11") (pin "7") (pinfunction "D3_7") (pintype "input"))
      (node (ref "U12") (pin "7") (pinfunction "Y2_7") (pintype "tri_state"))
      (node (ref "U13") (pin "14") (pinfunction "Y3_14") (pintype "tri_state"))
      (node (ref "U14") (pin "7") (pinfunction "Y2_7") (pintype "tri_state"))
      (node (ref "U15") (pin "6") (pinfunction "A5_6") (pintype "bidirectional"))
      (node (ref "U16") (pin "15") (pinfunction "5Q_15") (pintype "tri_state"))
      (node (ref "U21") (pin "9") (pinfunction "Y1_9") (pintype "tri_state"))
      (node (ref "U26") (pin "8") (pinfunction "D4_8") (pintype "input"))
    )
    (net (code "147") (name "BD5") (class "Default")
      (node (ref "PC0") (pin "48") (pinfunction "D5_48") (pintype "bidirectional"))
      (node (ref "U11") (pin "14") (pinfunction "D6_14") (pintype "input"))
      (node (ref "U12") (pin "14") (pinfunction "Y3_14") (pintype "tri_state"))
      (node (ref "U13") (pin "7") (pinfunction "Y2_7") (pintype "tri_state"))
      (node (ref "U14") (pin "14") (pinfunction "Y3_14") (pintype "tri_state"))
      (node (ref "U15") (pin "7") (pinfunction "A6_7") (pintype "bidirectional"))
      (node (ref "U16") (pin "14") (pinfunction "6Q_14") (pintype "tri_state"))
      (node (ref "U21") (pin "7") (pinfunction "Y2_7") (pintype "tri_state"))
      (node (ref "U26") (pin "7") (pinfunction "D3_7") (pintype "input"))
    )
    (net (code "148") (name "BD6") (class "Default")
      (node (ref "PC0") (pin "49") (pinfunction "D6_49") (pintype "bidirectional"))
      (node (ref "U11") (pin "13") (pinfunction "D5_13") (pintype "input"))
      (node (ref "U12") (pin "9") (pinfunction "Y1_9") (pintype "tri_state"))
      (node (ref "U13") (pin "12") (pinfunction "Y4_12") (pintype "tri_state"))
      (node (ref "U14") (pin "9") (pinfunction "Y1_9") (pintype "tri_state"))
      (node (ref "U15") (pin "8") (pinfunction "A7_8") (pintype "bidirectional"))
      (node (ref "U16") (pin "13") (pinfunction "7Q_13") (pintype "tri_state"))
      (node (ref "U21") (pin "5") (pinfunction "Y3_5") (pintype "tri_state"))
      (node (ref "U26") (pin "4") (pinfunction "D2_4") (pintype "input"))
    )
    (net (code "149") (name "BD7") (class "Default")
      (node (ref "PC0") (pin "50") (pinfunction "D7_50") (pintype "bidirectional"))
      (node (ref "U11") (pin "8") (pinfunction "D4_8") (pintype "input"))
      (node (ref "U12") (pin "12") (pinfunction "Y4_12") (pintype "tri_state"))
      (node (ref "U13") (pin "9") (pinfunction "Y1_9") (pintype "tri_state"))
      (node (ref "U14") (pin "12") (pinfunction "Y4_12") (pintype "tri_state"))
      (node (ref "U15") (pin "9") (pinfunction "A8_9") (pintype "bidirectional"))
      (node (ref "U16") (pin "12") (pinfunction "8Q_12") (pintype "tri_state"))
      (node (ref "U21") (pin "3") (pinfunction "Y4_3") (pintype "tri_state"))
      (node (ref "U26") (pin "3") (pinfunction "D1_3") (pintype "input"))
    )
    (net (code "150") (name "CPUINH") (class "Default")
      (node (ref "U15") (pin "19") (pinfunction "G_19") (pintype "input"))
      (node (ref "U24") (pin "1") (pinfunction "G_1") (pintype "input"))
      (node (ref "U24") (pin "19") (pinfunction "G_19") (pintype "input"))
      (node (ref "U25") (pin "1") (pinfunction "G_1") (pintype "input"))
      (node (ref "U25") (pin "19") (pinfunction "G_19") (pintype "input"))
      (node (ref "U29") (pin "15") (pinfunction "G_15") (pintype "input"))
      (node (ref "U5") (pin "15") (pinfunction "G_15") (pintype "input"))
      (node (ref "U8") (pin "1") (pinfunction "G_1") (pintype "input"))
      (node (ref "U9") (pin "5") (pinfunction "Q_5") (pintype "output"))
    )
    (net (code "151") (name "GND") (class "Default")
      (node (ref "C1") (pin "2") (pinfunction "2_2") (pintype "passive"))
      (node (ref "C10") (pin "2") (pinfunction "2_2") (pintype "passive"))
      (node (ref "C11") (pin "2") (pinfunction "2_2") (pintype "passive"))
      (node (ref "C12") (pin "2") (pinfunction "2_2") (pintype "passive"))
      (node (ref "C13") (pin "2") (pinfunction "2_2") (pintype "passive"))
      (node (ref "C14") (pin "2") (pinfunction "2_2") (pintype "passive"))
      (node (ref "C15") (pin "2") (pinfunction "2_2") (pintype "passive"))
      (node (ref "C16") (pin "2") (pinfunction "2_2") (pintype "passive"))
      (node (ref "C17") (pin "2") (pinfunction "2_2") (pintype "passive"))
      (node (ref "C18") (pin "2") (pinfunction "2_2") (pintype "passive"))
      (node (ref "C19") (pin "2") (pinfunction "2_2") (pintype "passive"))
      (node (ref "C2") (pin "2") (pinfunction "2_2") (pintype "passive"))
      (node (ref "C20") (pin "2") (pinfunction "2_2") (pintype "passive"))
      (node (ref "C21") (pin "2") (pinfunction "2_2") (pintype "passive"))
      (node (ref "C22") (pin "2") (pinfunction "2_2") (pintype "passive"))
      (node (ref "C23") (pin "2") (pinfunction "2_2") (pintype "passive"))
      (node (ref "C24") (pin "2") (pinfunction "2_2") (pintype "passive"))
      (node (ref "C25") (pin "2") (pinfunction "2_2") (pintype "passive"))
      (node (ref "C26") (pin "2") (pinfunction "2_2") (pintype "passive"))
      (node (ref "C27") (pin "2") (pinfunction "2_2") (pintype "passive"))
      (node (ref "C28") (pin "2") (pinfunction "2_2") (pintype "passive"))
      (node (ref "C29") (pin "2") (pinfunction "2_2") (pintype "passive"))
      (node (ref "C3") (pin "2") (pinfunction "2_2") (pintype "passive"))
      (node (ref "C30") (pin "2") (pinfunction "2_2") (pintype "passive"))
      (node (ref "C31") (pin "2") (pinfunction "2_2") (pintype "passive"))
      (node (ref "C32") (pin "2") (pinfunction "2_2") (pintype "passive"))
      (node (ref "C33") (pin "-") (pinfunction "-_-") (pintype "passive"))
      (node (ref "C4") (pin "2") (pinfunction "2_2") (pintype "passive"))
      (node (ref "C5") (pin "2") (pinfunction "2_2") (pintype "passive"))
      (node (ref "C6") (pin "2") (pinfunction "2_2") (pintype "passive"))
      (node (ref "C7") (pin "2") (pinfunction "2_2") (pintype "passive"))
      (node (ref "C8") (pin "2") (pinfunction "2_2") (pintype "passive"))
      (node (ref "C9") (pin "2") (pinfunction "2_2") (pintype "passive"))
      (node (ref "D1") (pin "K") (pinfunction "C_K") (pintype "passive"))
      (node (ref "PC0") (pin "3") (pinfunction "GND_3") (pintype "bidirectional"))
      (node (ref "PC0") (pin "4") (pinfunction "GND_4") (pintype "bidirectional"))
      (node (ref "PC0") (pin "62") (pinfunction "GND_62") (pintype "bidirectional"))
      (node (ref "R3") (pin "2") (pinfunction "2_2") (pintype "passive"))
      (node (ref "R4") (pin "2") (pinfunction "2_2") (pintype "passive"))
      (node (ref "U14") (pin "11") (pinfunction "A1_11") (pintype "input"))
      (node (ref "U14") (pin "13") (pinfunction "A2_13") (pintype "input"))
      (node (ref "U14") (pin "15") (pinfunction "A3_15") (pintype "input"))
      (node (ref "U14") (pin "17") (pinfunction "A4_17") (pintype "input"))
      (node (ref "U14") (pin "4") (pinfunction "A2_4") (pintype "input"))
      (node (ref "U14") (pin "6") (pinfunction "A3_6") (pintype "input"))
      (node (ref "U14") (pin "8") (pinfunction "A4_8") (pintype "input"))
      (node (ref "U16") (pin "2") (pinfunction "1D_2") (pintype "input"))
      (node (ref "U16") (pin "3") (pinfunction "2D_3") (pintype "input"))
      (node (ref "U16") (pin "8") (pinfunction "7D_8") (pintype "input"))
      (node (ref "U16") (pin "9") (pinfunction "8D_9") (pintype "input"))
      (node (ref "U23") (pin "5") (pinfunction "EI_5") (pintype "input"))
      (node (ref "U5") (pin "10") (pinfunction "3B_10") (pintype "input"))
      (node (ref "U5") (pin "13") (pinfunction "4B_13") (pintype "input"))
      (node (ref "U5") (pin "3") (pinfunction "1B_3") (pintype "input"))
      (node (ref "U5") (pin "6") (pinfunction "2B_6") (pintype "input"))
      (node (ref "U6") (pin "18") (pinfunction "Q7_18") (pintype "input"))
      (node (ref "U7") (pin "12") (pinfunction "Q4_12") (pintype "input"))
      (node (ref "U7") (pin "14") (pinfunction "Q5_14") (pintype "input"))
      (node (ref "U7") (pin "16") (pinfunction "Q6_16") (pintype "input"))
      (node (ref "U7") (pin "18") (pinfunction "Q7_18") (pintype "input"))
      (node (ref "U7") (pin "5") (pinfunction "Q1_5") (pintype "input"))
      (node (ref "U7") (pin "7") (pinfunction "Q2_7") (pintype "input"))
      (node (ref "U7") (pin "9") (pinfunction "Q3_9") (pintype "input"))
      (node (ref "U8") (pin "11") (pinfunction "A1_11") (pintype "input"))
      (node (ref "U8") (pin "19") (pinfunction "G_19") (pintype "input"))
      (node (ref "U8") (pin "8") (pinfunction "A4_8") (pintype "input"))
      (node (ref "U9") (pin "12") (pinfunction "D_12") (pintype "input"))
      (node (ref "Y1") (pin "4") (pinfunction "GND_4") (pintype "power_in"))
    )
    (net (code "152") (name "ID0") (class "Default")
      (node (ref "U13") (pin "2") (pinfunction "A1_2") (pintype "input"))
    )
    (net (code "153") (name "ID1") (class "Default")
      (node (ref "U13") (pin "17") (pinfunction "A4_17") (pintype "input"))
    )
    (net (code "154") (name "ID2") (class "Default")
      (node (ref "U13") (pin "4") (pinfunction "A2_4") (pintype "input"))
    )
    (net (code "155") (name "ID3") (class "Default")
      (node (ref "U13") (pin "15") (pinfunction "A3_15") (pintype "input"))
    )
    (net (code "156") (name "ID4") (class "Default")
      (node (ref "U13") (pin "6") (pinfunction "A3_6") (pintype "input"))
    )
    (net (code "157") (name "ID5") (class "Default")
      (node (ref "U13") (pin "13") (pinfunction "A2_13") (pintype "input"))
    )
    (net (code "158") (name "ID6") (class "Default")
      (node (ref "U13") (pin "8") (pinfunction "A4_8") (pintype "input"))
    )
    (net (code "159") (name "ID7") (class "Default")
      (node (ref "U13") (pin "11") (pinfunction "A1_11") (pintype "input"))
    )
    (net (code "160") (name "Net-(D1-PadA)") (class "Default")
      (node (ref "D1") (pin "A") (pinfunction "A_A") (pintype "passive"))
      (node (ref "R1") (pin "1") (pinfunction "1_1") (pintype "passive"))
    )
    (net (code "161") (name "Net-(Q1-B)") (class "Default")
      (node (ref "Q1") (pin "2") (pinfunction "B_2") (pintype "passive"))
      (node (ref "R2") (pin "2") (pinfunction "2_2") (pintype "passive"))
    )
    (net (code "162") (name "Net-(Q1-C)") (class "Default")
      (node (ref "Q1") (pin "3") (pinfunction "C_3") (pintype "passive"))
      (node (ref "R1") (pin "2") (pinfunction "2_2") (pintype "passive"))
    )
    (net (code "163") (name "Net-(U3A-I1)") (class "Default")
      (node (ref "U3") (pin "2") (pinfunction "I1_2") (pintype "input"))
      (node (ref "U4") (pin "6") (pinfunction "O_6") (pintype "output"))
    )
    (net (code "164") (name "Net-(U3B-O)") (class "Default")
      (node (ref "U3") (pin "6") (pinfunction "O_6") (pintype "output"))
      (node (ref "U4") (pin "5") (pinfunction "I_5") (pintype "input"))
    )
    (net (code "165") (name "Net-(U3C-I0)") (class "Default")
      (node (ref "JP3") (pin "1") (pinfunction "1_1") (pintype "passive"))
      (node (ref "R3") (pin "1") (pinfunction "1_1") (pintype "passive"))
      (node (ref "U3") (pin "9") (pinfunction "I0_9") (pintype "input"))
    )
    (net (code "166") (name "Net-(U3C-I1)") (class "Default")
      (node (ref "U3") (pin "10") (pinfunction "I1_10") (pintype "input"))
      (node (ref "U3") (pin "11") (pinfunction "O_11") (pintype "output"))
    )
    (net (code "167") (name "Net-(U3D-I0)") (class "Default")
      (node (ref "U3") (pin "12") (pinfunction "I0_12") (pintype "input"))
      (node (ref "U4") (pin "8") (pinfunction "O_8") (pintype "output"))
    )
    (net (code "168") (name "Net-(U3D-I1)") (class "Default")
      (node (ref "U3") (pin "13") (pinfunction "I1_13") (pintype "input"))
      (node (ref "U7") (pin "19") (pinfunction "P=Q_19") (pintype "output"))
    )
    (net (code "169") (name "Net-(U4A-O)") (class "Default")
      (node (ref "U4") (pin "2") (pinfunction "O_2") (pintype "output"))
      (node (ref "U7") (pin "1") (pinfunction "G_1") (pintype "input"))
    )
    (net (code "170") (name "Net-(U4B-I)") (class "Default")
      (node (ref "U4") (pin "12") (pinfunction "O_12") (pintype "output"))
      (node (ref "U4") (pin "3") (pinfunction "I_3") (pintype "input"))
    )
    (net (code "171") (name "Net-(U4B-O)") (class "Default")
      (node (ref "U4") (pin "4") (pinfunction "O_4") (pintype "output"))
      (node (ref "U9") (pin "3") (pinfunction "CLK_3") (pintype "input"))
    )
    (net (code "172") (name "Net-(U6A-G)") (class "Default")
      (node (ref "JP4") (pin "2") (pinfunction "2_2") (pintype "passive"))
      (node (ref "R4") (pin "1") (pinfunction "1_1") (pintype "passive"))
      (node (ref "U6") (pin "1") (pinfunction "G_1") (pintype "input"))
    )
    (net (code "173") (name "Net-(U10A-Q)") (class "Default")
      (node (ref "U10") (pin "5") (pinfunction "Q_5") (pintype "output"))
      (node (ref "U12") (pin "17") (pinfunction "A4_17") (pintype "input"))
      (node (ref "U29") (pin "2") (pinfunction "1A_2") (pintype "input"))
    )
    (net (code "174") (name "Net-(U10B-CLR)") (class "Default")
      (node (ref "U10") (pin "13") (pinfunction "CLR_13") (pintype "input"))
      (node (ref "U18") (pin "6") (pinfunction "O_6") (pintype "output"))
    )
    (net (code "175") (name "Net-(U11A-Q2)") (class "Default")
      (node (ref "U11") (pin "5") (pinfunction "Q2_5") (pintype "output"))
      (node (ref "U12") (pin "4") (pinfunction "A2_4") (pintype "input"))
      (node (ref "U5") (pin "11") (pinfunction "3A_11") (pintype "input"))
    )
    (net (code "176") (name "Net-(U11A-Q3)") (class "Default")
      (node (ref "U11") (pin "6") (pinfunction "Q3_6") (pintype "output"))
      (node (ref "U12") (pin "13") (pinfunction "A2_13") (pintype "input"))
      (node (ref "U5") (pin "14") (pinfunction "4A_14") (pintype "input"))
    )
    (net (code "177") (name "Net-(U11A-Q4)") (class "Default")
      (node (ref "U11") (pin "9") (pinfunction "Q4_9") (pintype "output"))
      (node (ref "U12") (pin "8") (pinfunction "A4_8") (pintype "input"))
      (node (ref "U4") (pin "1") (pinfunction "I_1") (pintype "input"))
    )
    (net (code "178") (name "Net-(U11A-Q5)") (class "Default")
      (node (ref "U11") (pin "12") (pinfunction "Q5_12") (pintype "output"))
      (node (ref "U12") (pin "11") (pinfunction "A1_11") (pintype "input"))
    )
    (net (code "179") (name "Net-(U11A-Q6)") (class "Default")
      (node (ref "U11") (pin "15") (pinfunction "Q6_15") (pintype "output"))
      (node (ref "U12") (pin "6") (pinfunction "A3_6") (pintype "input"))
    )
    (net (code "180") (name "Net-(U11A-Q7)") (class "Default")
      (node (ref "U11") (pin "16") (pinfunction "Q7_16") (pintype "output"))
      (node (ref "U12") (pin "15") (pinfunction "A3_15") (pintype "input"))
      (node (ref "U5") (pin "5") (pinfunction "2A_5") (pintype "input"))
    )
    (net (code "181") (name "Net-(U11A-Q8)") (class "Default")
      (node (ref "U11") (pin "19") (pinfunction "Q8_19") (pintype "output"))
      (node (ref "U12") (pin "2") (pinfunction "A1_2") (pintype "input"))
      (node (ref "U5") (pin "2") (pinfunction "1A_2") (pintype "input"))
    )
    (net (code "182") (name "Net-(U13A-G)") (class "Default")
      (node (ref "U1") (pin "7") (pinfunction "Y7_7") (pintype "output"))
      (node (ref "U13") (pin "1") (pinfunction "G_1") (pintype "input"))
      (node (ref "U13") (pin "19") (pinfunction "G_19") (pintype "input"))
    )
    (net (code "183") (name "Net-(U14A-G)") (class "Default")
      (node (ref "U14") (pin "1") (pinfunction "G_1") (pintype "input"))
      (node (ref "U14") (pin "19") (pinfunction "G_19") (pintype "input"))
      (node (ref "U22") (pin "7") (pinfunction "Y7_7") (pintype "output"))
    )
    (net (code "184") (name "Net-(U15A-B1)") (class "Default")
      (node (ref "U15") (pin "18") (pinfunction "B1_18") (pintype "bidirectional"))
      (node (ref "U20") (pin "33") (pinfunction "D0_33") (pintype "bidirectional"))
    )
    (net (code "185") (name "Net-(U15A-B2)") (class "Default")
      (node (ref "U15") (pin "17") (pinfunction "B2_17") (pintype "bidirectional"))
      (node (ref "U20") (pin "32") (pinfunction "D1_32") (pintype "bidirectional"))
    )
    (net (code "186") (name "Net-(U15A-B3)") (class "Default")
      (node (ref "U15") (pin "16") (pinfunction "B3_16") (pintype "bidirectional"))
      (node (ref "U20") (pin "31") (pinfunction "D2_31") (pintype "bidirectional"))
    )
    (net (code "187") (name "Net-(U15A-B4)") (class "Default")
      (node (ref "U15") (pin "15") (pinfunction "B4_15") (pintype "bidirectional"))
      (node (ref "U20") (pin "30") (pinfunction "D3_30") (pintype "bidirectional"))
    )
    (net (code "188") (name "Net-(U15A-B5)") (class "Default")
      (node (ref "U15") (pin "14") (pinfunction "B5_14") (pintype "bidirectional"))
      (node (ref "U20") (pin "29") (pinfunction "D4_29") (pintype "bidirectional"))
    )
    (net (code "189") (name "Net-(U15A-B6)") (class "Default")
      (node (ref "U15") (pin "13") (pinfunction "B6_13") (pintype "bidirectional"))
      (node (ref "U20") (pin "28") (pinfunction "D5_28") (pintype "bidirectional"))
    )
    (net (code "190") (name "Net-(U15A-B7)") (class "Default")
      (node (ref "U15") (pin "12") (pinfunction "B7_12") (pintype "bidirectional"))
      (node (ref "U20") (pin "27") (pinfunction "D6_27") (pintype "bidirectional"))
    )
    (net (code "191") (name "Net-(U15A-B8)") (class "Default")
      (node (ref "U15") (pin "11") (pinfunction "B8_11") (pintype "bidirectional"))
      (node (ref "U20") (pin "26") (pinfunction "D7_26") (pintype "bidirectional"))
    )
    (net (code "192") (name "Net-(U15A-DIR)") (class "Default")
      (node (ref "U15") (pin "1") (pinfunction "DIR_1") (pintype "input"))
      (node (ref "U17") (pin "1") (pinfunction "I0_1") (pintype "input"))
      (node (ref "U19") (pin "3") (pinfunction "I_3") (pintype "input"))
      (node (ref "U20") (pin "34") (pinfunction "R~{WB}_34") (pintype "output"))
    )
    (net (code "193") (name "Net-(U16A-3D)") (class "Default")
      (node (ref "U16") (pin "4") (pinfunction "3D_4") (pintype "input"))
      (node (ref "U23") (pin "9") (pinfunction "A0_9") (pintype "output"))
    )
    (net (code "194") (name "Net-(U16A-4D)") (class "Default")
      (node (ref "U16") (pin "5") (pinfunction "4D_5") (pintype "input"))
      (node (ref "U23") (pin "7") (pinfunction "A1_7") (pintype "output"))
    )
    (net (code "195") (name "Net-(U16A-5D)") (class "Default")
      (node (ref "U16") (pin "6") (pinfunction "5D_6") (pintype "input"))
      (node (ref "U23") (pin "6") (pinfunction "A2_6") (pintype "output"))
    )
    (net (code "196") (name "Net-(U16A-6D)") (class "Default")
      (node (ref "U16") (pin "7") (pinfunction "6D_7") (pintype "input"))
      (node (ref "U19") (pin "10") (pinfunction "O_10") (pintype "output"))
    )
    (net (code "197") (name "Net-(U17A-I1)") (class "Default")
      (node (ref "JP1") (pin "2") (pinfunction "2_2") (pintype "passive"))
      (node (ref "U17") (pin "2") (pinfunction "I1_2") (pintype "input"))
      (node (ref "U17") (pin "4") (pinfunction "I0_4") (pintype "input"))
      (node (ref "U20") (pin "37") (pinfunction "PHI2_37") (pintype "input"))
      (node (ref "U8") (pin "17") (pinfunction "A4_17") (pintype "input"))
    )
    (net (code "198") (name "Net-(U17B-I1)") (class "Default")
      (node (ref "U17") (pin "5") (pinfunction "I1_5") (pintype "input"))
      (node (ref "U19") (pin "4") (pinfunction "O_4") (pintype "output"))
    )
    (net (code "199") (name "Net-(U17C-I1)") (class "Default")
      (node (ref "U17") (pin "10") (pinfunction "I1_10") (pintype "input"))
      (node (ref "U19") (pin "12") (pinfunction "O_12") (pintype "output"))
    )
    (net (code "200") (name "Net-(U17D-I0)") (class "Default")
      (node (ref "U17") (pin "12") (pinfunction "I0_12") (pintype "input"))
      (node (ref "U18") (pin "11") (pinfunction "O_11") (pintype "output"))
    )
    (net (code "201") (name "Net-(U17D-I1)") (class "Default")
      (node (ref "U17") (pin "13") (pinfunction "I1_13") (pintype "input"))
      (node (ref "U19") (pin "6") (pinfunction "O_6") (pintype "output"))
    )
    (net (code "202") (name "Net-(U18A-I0)") (class "Default")
      (node (ref "U18") (pin "1") (pinfunction "I0_1") (pintype "input"))
      (node (ref "U4") (pin "10") (pinfunction "O_10") (pintype "output"))
    )
    (net (code "203") (name "Net-(U18A-O)") (class "Default")
      (node (ref "U18") (pin "3") (pinfunction "O_3") (pintype "output"))
      (node (ref "U9") (pin "2") (pinfunction "D_2") (pintype "input"))
    )
    (net (code "204") (name "Net-(U18C-O)") (class "Default")
      (node (ref "U18") (pin "8") (pinfunction "O_8") (pintype "output"))
      (node (ref "U20") (pin "4") (pinfunction "~{IRQB}_4") (pintype "input"))
    )
    (net (code "205") (name "Net-(U19D-I)") (class "Default")
      (node (ref "U19") (pin "9") (pinfunction "I_9") (pintype "input"))
      (node (ref "U20") (pin "7") (pinfunction "SYNC_7") (pintype "output"))
    )
    (net (code "206") (name "Net-(U19D-O)") (class "Default")
      (node (ref "U19") (pin "8") (pinfunction "O_8") (pintype "output"))
      (node (ref "U8") (pin "6") (pinfunction "A3_6") (pintype "input"))
    )
    (net (code "207") (name "Net-(U19E-I)") (class "Default")
      (node (ref "U19") (pin "11") (pinfunction "I_11") (pintype "input"))
      (node (ref "U23") (pin "15") (pinfunction "EO_15") (pintype "output"))
    )
    (net (code "208") (name "Net-(U20A-~{NMIB})") (class "Default")
      (node (ref "JP5") (pin "2") (pinfunction "2_2") (pintype "passive"))
      (node (ref "R6") (pin "1") (pinfunction "1_1") (pintype "passive"))
      (node (ref "U20") (pin "6") (pinfunction "~{NMIB}_6") (pintype "input"))
    )
    (net (code "209") (name "Net-(U21A-A1)") (class "Default")
      (node (ref "U21") (pin "2") (pinfunction "A1_2") (pintype "input"))
      (node (ref "U26") (pin "19") (pinfunction "Q8_19") (pintype "output"))
      (node (ref "U27") (pin "1") (pinfunction "I0_1") (pintype "input"))
    )
    (net (code "210") (name "Net-(U21A-A2)") (class "Default")
      (node (ref "U21") (pin "4") (pinfunction "A2_4") (pintype "input"))
      (node (ref "U26") (pin "16") (pinfunction "Q7_16") (pintype "output"))
      (node (ref "U27") (pin "4") (pinfunction "I0_4") (pintype "input"))
    )
    (net (code "211") (name "Net-(U21A-A3)") (class "Default")
      (node (ref "U21") (pin "6") (pinfunction "A3_6") (pintype "input"))
      (node (ref "U26") (pin "15") (pinfunction "Q6_15") (pintype "output"))
      (node (ref "U27") (pin "12") (pinfunction "I0_12") (pintype "input"))
    )
    (net (code "212") (name "Net-(U21A-A4)") (class "Default")
      (node (ref "U21") (pin "8") (pinfunction "A4_8") (pintype "input"))
      (node (ref "U26") (pin "12") (pinfunction "Q5_12") (pintype "output"))
      (node (ref "U27") (pin "9") (pinfunction "I0_9") (pintype "input"))
    )
    (net (code "213") (name "Net-(U21B-A1)") (class "Default")
      (node (ref "U21") (pin "11") (pinfunction "A1_11") (pintype "input"))
      (node (ref "U26") (pin "9") (pinfunction "Q4_9") (pintype "output"))
      (node (ref "U28") (pin "4") (pinfunction "I0_4") (pintype "input"))
    )
    (net (code "214") (name "Net-(U21B-A2)") (class "Default")
      (node (ref "U21") (pin "13") (pinfunction "A2_13") (pintype "input"))
      (node (ref "U26") (pin "6") (pinfunction "Q3_6") (pintype "output"))
      (node (ref "U28") (pin "1") (pinfunction "I0_1") (pintype "input"))
    )
    (net (code "215") (name "Net-(U21B-A3)") (class "Default")
      (node (ref "U21") (pin "15") (pinfunction "A3_15") (pintype "input"))
      (node (ref "U26") (pin "5") (pinfunction "Q2_5") (pintype "output"))
      (node (ref "U28") (pin "12") (pinfunction "I0_12") (pintype "input"))
    )
    (net (code "216") (name "Net-(U21B-A4)") (class "Default")
      (node (ref "U21") (pin "17") (pinfunction "A4_17") (pintype "input"))
      (node (ref "U26") (pin "2") (pinfunction "Q1_2") (pintype "output"))
      (node (ref "U28") (pin "9") (pinfunction "I0_9") (pintype "input"))
    )
    (net (code "217") (name "Net-(U23A-0)") (class "Default")
      (node (ref "U23") (pin "10") (pinfunction "0_10") (pintype "input"))
      (node (ref "U28") (pin "8") (pinfunction "O_8") (pintype "output"))
    )
    (net (code "218") (name "Net-(U23A-1)") (class "Default")
      (node (ref "U23") (pin "11") (pinfunction "1_11") (pintype "input"))
      (node (ref "U28") (pin "11") (pinfunction "O_11") (pintype "output"))
    )
    (net (code "219") (name "Net-(U23A-2)") (class "Default")
      (node (ref "U23") (pin "12") (pinfunction "2_12") (pintype "input"))
      (node (ref "U28") (pin "3") (pinfunction "O_3") (pintype "output"))
    )
    (net (code "220") (name "Net-(U23A-3)") (class "Default")
      (node (ref "U23") (pin "13") (pinfunction "3_13") (pintype "input"))
      (node (ref "U28") (pin "6") (pinfunction "O_6") (pintype "output"))
    )
    (net (code "221") (name "Net-(U23A-4)") (class "Default")
      (node (ref "U23") (pin "1") (pinfunction "4_1") (pintype "input"))
      (node (ref "U27") (pin "8") (pinfunction "O_8") (pintype "output"))
    )
    (net (code "222") (name "Net-(U23A-5)") (class "Default")
      (node (ref "U23") (pin "2") (pinfunction "5_2") (pintype "input"))
      (node (ref "U27") (pin "11") (pinfunction "O_11") (pintype "output"))
    )
    (net (code "223") (name "Net-(U23A-6)") (class "Default")
      (node (ref "U23") (pin "3") (pinfunction "6_3") (pintype "input"))
      (node (ref "U27") (pin "6") (pinfunction "O_6") (pintype "output"))
    )
    (net (code "224") (name "Net-(U23A-7)") (class "Default")
      (node (ref "U23") (pin "4") (pinfunction "7_4") (pintype "input"))
      (node (ref "U27") (pin "3") (pinfunction "O_3") (pintype "output"))
    )
    (net (code "225") (name "Net-(U29A-~{A}{slash}B)") (class "Default")
      (node (ref "U29") (pin "1") (pinfunction "~{A}/B_1") (pintype "input"))
      (node (ref "U3") (pin "8") (pinfunction "O_8") (pintype "output"))
      (node (ref "U5") (pin "1") (pinfunction "~{A}/B_1") (pintype "input"))
    )
    (net (code "226") (name "Net-(U30A-CLK)") (class "Default")
      (node (ref "JP1") (pin "3") (pinfunction "3_3") (pintype "passive"))
      (node (ref "U30") (pin "11") (pinfunction "CLK_11") (pintype "input"))
      (node (ref "U30") (pin "3") (pinfunction "CLK_3") (pintype "input"))
      (node (ref "Y1") (pin "5") (pinfunction "FO_5") (pintype "output"))
    )
    (net (code "227") (name "Net-(U30A-D)") (class "Default")
      (node (ref "U3") (pin "3") (pinfunction "O_3") (pintype "output"))
      (node (ref "U30") (pin "2") (pinfunction "D_2") (pintype "input"))
    )
    (net (code "228") (name "Net-(U30A-Q)") (class "Default")
      (node (ref "JP1") (pin "1") (pinfunction "1_1") (pintype "passive"))
      (node (ref "JP2") (pin "3") (pinfunction "3_3") (pintype "passive"))
      (node (ref "U3") (pin "1") (pinfunction "I0_1") (pintype "input"))
      (node (ref "U30") (pin "5") (pinfunction "Q_5") (pintype "output"))
    )
    (net (code "229") (name "Net-(U30B-D)") (class "Default")
      (node (ref "JP2") (pin "2") (pinfunction "2_2") (pintype "passive"))
      (node (ref "U30") (pin "12") (pinfunction "D_12") (pintype "input"))
    )
    (net (code "230") (name "Net-(U30B-Q)") (class "Default")
      (node (ref "U3") (pin "5") (pinfunction "I1_5") (pintype "input"))
      (node (ref "U30") (pin "9") (pinfunction "Q_9") (pintype "output"))
    )
    (net (code "231") (name "Net-(U31A-O)") (class "Default")
      (node (ref "U31") (pin "11") (pinfunction "I_11") (pintype "input"))
      (node (ref "U31") (pin "12") (pinfunction "O_12") (pintype "output"))
    )
    (net (code "232") (name "Net-(U31B-O)") (class "Default")
      (node (ref "U3") (pin "4") (pinfunction "I0_4") (pintype "input"))
      (node (ref "U31") (pin "10") (pinfunction "O_10") (pintype "output"))
    )
    (net (code "233") (name "Net-(U31D-O)") (class "Default")
      (node (ref "U31") (pin "2") (pinfunction "O_2") (pintype "output"))
      (node (ref "U31") (pin "3") (pinfunction "I_3") (pintype "input"))
    )
    (net (code "234") (name "Net-(Y1-OE)") (class "Default")
      (node (ref "R5") (pin "1") (pinfunction "1_1") (pintype "passive"))
      (node (ref "Y1") (pin "1") (pinfunction "OE_1") (pintype "input"))
    )
    (net (code "235") (name "PH1") (class "Default")
      (node (ref "U16") (pin "11") (pinfunction "CLK_11") (pintype "input"))
      (node (ref "U20") (pin "3") (pinfunction "PHI1O_3") (pintype "output"))
      (node (ref "U9") (pin "11") (pinfunction "CLK_11") (pintype "input"))
    )
    (net (code "236") (name "PH2") (class "Default")
      (node (ref "U20") (pin "39") (pinfunction "PHI2O_39") (pintype "output"))
      (node (ref "U4") (pin "13") (pinfunction "I_13") (pintype "input"))
    )
    (net (code "237") (name "RDY") (class "Default")
      (node (ref "R7") (pin "1") (pinfunction "1_1") (pintype "passive"))
      (node (ref "U19") (pin "13") (pinfunction "I_13") (pintype "input"))
      (node (ref "U20") (pin "2") (pinfunction "RDY_2") (pintype "bidirectional"))
    )
    (net (code "238") (name "VCC") (class "Default")
      (node (ref "C1") (pin "1") (pinfunction "1_1") (pintype "passive"))
      (node (ref "C10") (pin "1") (pinfunction "1_1") (pintype "passive"))
      (node (ref "C11") (pin "1") (pinfunction "1_1") (pintype "passive"))
      (node (ref "C12") (pin "1") (pinfunction "1_1") (pintype "passive"))
      (node (ref "C13") (pin "1") (pinfunction "1_1") (pintype "passive"))
      (node (ref "C14") (pin "1") (pinfunction "1_1") (pintype "passive"))
      (node (ref "C15") (pin "1") (pinfunction "1_1") (pintype "passive"))
      (node (ref "C16") (pin "1") (pinfunction "1_1") (pintype "passive"))
      (node (ref "C17") (pin "1") (pinfunction "1_1") (pintype "passive"))
      (node (ref "C18") (pin "1") (pinfunction "1_1") (pintype "passive"))
      (node (ref "C19") (pin "1") (pinfunction "1_1") (pintype "passive"))
      (node (ref "C2") (pin "1") (pinfunction "1_1") (pintype "passive"))
      (node (ref "C20") (pin "1") (pinfunction "1_1") (pintype "passive"))
      (node (ref "C21") (pin "1") (pinfunction "1_1") (pintype "passive"))
      (node (ref "C22") (pin "1") (pinfunction "1_1") (pintype "passive"))
      (node (ref "C23") (pin "1") (pinfunction "1_1") (pintype "passive"))
      (node (ref "C24") (pin "1") (pinfunction "1_1") (pintype "passive"))
      (node (ref "C25") (pin "1") (pinfunction "1_1") (pintype "passive"))
      (node (ref "C26") (pin "1") (pinfunction "1_1") (pintype "passive"))
      (node (ref "C27") (pin "1") (pinfunction "1_1") (pintype "passive"))
      (node (ref "C28") (pin "1") (pinfunction "1_1") (pintype "passive"))
      (node (ref "C29") (pin "1") (pinfunction "1_1") (pintype "passive"))
      (node (ref "C3") (pin "1") (pinfunction "1_1") (pintype "passive"))
      (node (ref "C30") (pin "1") (pinfunction "1_1") (pintype "passive"))
      (node (ref "C31") (pin "1") (pinfunction "1_1") (pintype "passive"))
      (node (ref "C32") (pin "1") (pinfunction "1_1") (pintype "passive"))
      (node (ref "C33") (pin "+") (pinfunction "+_+") (pintype "passive"))
      (node (ref "C4") (pin "1") (pinfunction "1_1") (pintype "passive"))
      (node (ref "C5") (pin "1") (pinfunction "1_1") (pintype "passive"))
      (node (ref "C6") (pin "1") (pinfunction "1_1") (pintype "passive"))
      (node (ref "C7") (pin "1") (pinfunction "1_1") (pintype "passive"))
      (node (ref "C8") (pin "1") (pinfunction "1_1") (pintype "passive"))
      (node (ref "C9") (pin "1") (pinfunction "1_1") (pintype "passive"))
      (node (ref "JP2") (pin "1") (pinfunction "1_1") (pintype "passive"))
      (node (ref "JP4") (pin "1") (pinfunction "1_1") (pintype "passive"))
      (node (ref "PC0") (pin "5") (pinfunction "+5V_5") (pintype "bidirectional"))
      (node (ref "PC0") (pin "6") (pinfunction "+5V_6") (pintype "bidirectional"))
      (node (ref "Q1") (pin "1") (pinfunction "E_1") (pintype "passive"))
      (node (ref "R5") (pin "2") (pinfunction "2_2") (pintype "passive"))
      (node (ref "R6") (pin "2") (pinfunction "2_2") (pintype "passive"))
      (node (ref "U10") (pin "1") (pinfunction "CLR_1") (pintype "input"))
      (node (ref "U10") (pin "11") (pinfunction "CLK_11") (pintype "input"))
      (node (ref "U10") (pin "12") (pinfunction "D_12") (pintype "input"))
      (node (ref "U11") (pin "3") (pinfunction "D1_3") (pintype "input"))
      (node (ref "U14") (pin "2") (pinfunction "A1_2") (pintype "input"))
      (node (ref "U19") (pin "1") (pinfunction "I_1") (pintype "input"))
      (node (ref "U2") (pin "6") (pinfunction "G1_6") (pintype "input"))
      (node (ref "U20") (pin "36") (pinfunction "BE_36") (pintype "input"))
      (node (ref "U20") (pin "38") (pinfunction "~{SOB}_38") (pintype "input"))
      (node (ref "U22") (pin "6") (pinfunction "G1_6") (pintype "input"))
      (node (ref "U29") (pin "10") (pinfunction "3B_10") (pintype "input"))
      (node (ref "U29") (pin "11") (pinfunction "3A_11") (pintype "input"))
      (node (ref "U29") (pin "13") (pinfunction "4B_13") (pintype "input"))
      (node (ref "U29") (pin "14") (pinfunction "4A_14") (pintype "input"))
      (node (ref "U29") (pin "5") (pinfunction "2A_5") (pintype "input"))
      (node (ref "U29") (pin "6") (pinfunction "2B_6") (pintype "input"))
      (node (ref "U30") (pin "1") (pinfunction "CLR_1") (pintype "input"))
      (node (ref "U30") (pin "10") (pinfunction "PRE_10") (pintype "input"))
      (node (ref "U30") (pin "13") (pinfunction "CLR_13") (pintype "input"))
      (node (ref "U30") (pin "4") (pinfunction "PRE_4") (pintype "input"))
      (node (ref "U31") (pin "5") (pinfunction "I_5") (pintype "input"))
      (node (ref "U31") (pin "9") (pinfunction "I_9") (pintype "input"))
      (node (ref "U6") (pin "12") (pinfunction "Q4_12") (pintype "input"))
      (node (ref "U6") (pin "14") (pinfunction "Q5_14") (pintype "input"))
      (node (ref "U6") (pin "16") (pinfunction "Q6_16") (pintype "input"))
      (node (ref "U6") (pin "2") (pinfunction "P0_2") (pintype "input"))
      (node (ref "U6") (pin "3") (pinfunction "Q0_3") (pintype "input"))
      (node (ref "U6") (pin "4") (pinfunction "P1_4") (pintype "input"))
      (node (ref "U6") (pin "5") (pinfunction "Q1_5") (pintype "input"))
      (node (ref "U6") (pin "6") (pinfunction "P2_6") (pintype "input"))
      (node (ref "U6") (pin "7") (pinfunction "Q2_7") (pintype "input"))
      (node (ref "U6") (pin "8") (pinfunction "P3_8") (pintype "input"))
      (node (ref "U6") (pin "9") (pinfunction "Q3_9") (pintype "input"))
      (node (ref "U7") (pin "2") (pinfunction "P0_2") (pintype "input"))
      (node (ref "U7") (pin "3") (pinfunction "Q0_3") (pintype "input"))
      (node (ref "U9") (pin "4") (pinfunction "PRE_4") (pintype "input"))
      (node (ref "Y1") (pin "8") (pinfunction "VCC_8") (pintype "power_in"))
    )
    (net (code "239") (name "unconnected-(PC0-+3.3V-Pad2)") (class "Default")
      (node (ref "PC0") (pin "2") (pinfunction "+3.3V_2") (pintype "bidirectional"))
    )
    (net (code "240") (name "unconnected-(PC0-+5VSB-Pad8)") (class "Default")
      (node (ref "PC0") (pin "8") (pinfunction "+5VSB_8") (pintype "bidirectional"))
    )
    (net (code "241") (name "unconnected-(PC0-+12V-Pad1)") (class "Default")
      (node (ref "PC0") (pin "1") (pinfunction "+12V_1") (pintype "bidirectional"))
    )
    (net (code "242") (name "unconnected-(PC0--12V-Pad7)") (class "Default")
      (node (ref "PC0") (pin "7") (pinfunction "-12V_7") (pintype "bidirectional"))
    )
    (net (code "243") (name "unconnected-(PC0-~{BUSRQ}-Pad10)") (class "Default")
      (node (ref "PC0") (pin "10") (pinfunction "~{BUSRQ}_10") (pintype "bidirectional"))
    )
    (net (code "244") (name "unconnected-(PC0-~{CINH}-Pad13)") (class "Default")
      (node (ref "PC0") (pin "13") (pinfunction "~{CINH}_13") (pintype "bidirectional"))
    )
    (net (code "245") (name "unconnected-(U1A-Y0-Pad15)") (class "Default")
      (node (ref "U1") (pin "15") (pinfunction "Y0_15") (pintype "output"))
    )
    (net (code "246") (name "unconnected-(U1A-Y1-Pad14)") (class "Default")
      (node (ref "U1") (pin "14") (pinfunction "Y1_14") (pintype "output"))
    )
    (net (code "247") (name "unconnected-(U1A-Y2-Pad13)") (class "Default")
      (node (ref "U1") (pin "13") (pinfunction "Y2_13") (pintype "output"))
    )
    (net (code "248") (name "unconnected-(U1A-Y3-Pad12)") (class "Default")
      (node (ref "U1") (pin "12") (pinfunction "Y3_12") (pintype "output"))
    )
    (net (code "249") (name "unconnected-(U1A-Y4-Pad11)") (class "Default")
      (node (ref "U1") (pin "11") (pinfunction "Y4_11") (pintype "output"))
    )
    (net (code "250") (name "unconnected-(U1A-Y5-Pad10)") (class "Default")
      (node (ref "U1") (pin "10") (pinfunction "Y5_10") (pintype "output"))
    )
    (net (code "251") (name "unconnected-(U1A-Y6-Pad9)") (class "Default")
      (node (ref "U1") (pin "9") (pinfunction "Y6_9") (pintype "output"))
    )
    (net (code "252") (name "unconnected-(U2A-Y0-Pad15)") (class "Default")
      (node (ref "U2") (pin "15") (pinfunction "Y0_15") (pintype "output"))
    )
    (net (code "253") (name "unconnected-(U2A-Y1-Pad14)") (class "Default")
      (node (ref "U2") (pin "14") (pinfunction "Y1_14") (pintype "output"))
    )
    (net (code "254") (name "unconnected-(U2A-Y6-Pad9)") (class "Default")
      (node (ref "U2") (pin "9") (pinfunction "Y6_9") (pintype "output"))
    )
    (net (code "255") (name "unconnected-(U2A-Y7-Pad7)") (class "Default")
      (node (ref "U2") (pin "7") (pinfunction "Y7_7") (pintype "output"))
    )
    (net (code "256") (name "unconnected-(U8A-Y4-Pad12)") (class "Default")
      (node (ref "U8") (pin "12") (pinfunction "Y4_12") (pintype "tri_state"))
    )
    (net (code "257") (name "unconnected-(U8B-Y1-Pad9)") (class "Default")
      (node (ref "U8") (pin "9") (pinfunction "Y1_9") (pintype "tri_state"))
    )
    (net (code "258") (name "unconnected-(U9B-Q-Pad9)") (class "Default")
      (node (ref "U9") (pin "9") (pinfunction "Q_9") (pintype "output"))
    )
    (net (code "259") (name "unconnected-(U10A-~{Q}-Pad6)") (class "Default")
      (node (ref "U10") (pin "6") (pinfunction "~{Q}_6") (pintype "output"))
    )
    (net (code "260") (name "unconnected-(U10B-Q-Pad9)") (class "Default")
      (node (ref "U10") (pin "9") (pinfunction "Q_9") (pintype "output"))
    )
    (net (code "261") (name "unconnected-(U11A-Q1-Pad2)") (class "Default")
      (node (ref "U11") (pin "2") (pinfunction "Q1_2") (pintype "output"))
    )
    (net (code "262") (name "unconnected-(U19A-O-Pad2)") (class "Default")
      (node (ref "U19") (pin "2") (pinfunction "O_2") (pintype "output"))
    )
    (net (code "263") (name "unconnected-(U22A-Y0-Pad15)") (class "Default")
      (node (ref "U22") (pin "15") (pinfunction "Y0_15") (pintype "output"))
    )
    (net (code "264") (name "unconnected-(U22A-Y1-Pad14)") (class "Default")
      (node (ref "U22") (pin "14") (pinfunction "Y1_14") (pintype "output"))
    )
    (net (code "265") (name "unconnected-(U22A-Y2-Pad13)") (class "Default")
      (node (ref "U22") (pin "13") (pinfunction "Y2_13") (pintype "output"))
    )
    (net (code "266") (name "unconnected-(U22A-Y3-Pad12)") (class "Default")
      (node (ref "U22") (pin "12") (pinfunction "Y3_12") (pintype "output"))
    )
    (net (code "267") (name "unconnected-(U22A-Y4-Pad11)") (class "Default")
      (node (ref "U22") (pin "11") (pinfunction "Y4_11") (pintype "output"))
    )
    (net (code "268") (name "unconnected-(U22A-Y5-Pad10)") (class "Default")
      (node (ref "U22") (pin "10") (pinfunction "Y5_10") (pintype "output"))
    )
    (net (code "269") (name "unconnected-(U29A-2Y-Pad7)") (class "Default")
      (node (ref "U29") (pin "7") (pinfunction "2Y_7") (pintype "tri_state"))
    )
    (net (code "270") (name "unconnected-(U29A-3Y-Pad9)") (class "Default")
      (node (ref "U29") (pin "9") (pinfunction "3Y_9") (pintype "tri_state"))
    )
    (net (code "271") (name "unconnected-(U29A-4Y-Pad12)") (class "Default")
      (node (ref "U29") (pin "12") (pinfunction "4Y_12") (pintype "tri_state"))
    )
    (net (code "272") (name "unconnected-(U30A-~{Q}-Pad6)") (class "Default")
      (node (ref "U30") (pin "6") (pinfunction "~{Q}_6") (pintype "output"))
    )
    (net (code "273") (name "unconnected-(U30B-~{Q}-Pad8)") (class "Default")
      (node (ref "U30") (pin "8") (pinfunction "~{Q}_8") (pintype "output"))
    )
    (net (code "274") (name "unconnected-(U31C-O-Pad8)") (class "Default")
      (node (ref "U31") (pin "8") (pinfunction "O_8") (pintype "output"))
    )
    (net (code "275") (name "unconnected-(U31F-O-Pad6)") (class "Default")
      (node (ref "U31") (pin "6") (pinfunction "O_6") (pintype "output"))
    )
    (net (code "276") (name "~{BBUSACK}") (class "Default")
      (node (ref "PC0") (pin "20") (pinfunction "~{BUSACK}_20") (pintype "bidirectional"))
      (node (ref "U8") (pin "7") (pinfunction "Y2_7") (pintype "tri_state"))
    )
    (net (code "277") (name "~{BCBR}") (class "Default")
      (node (ref "PC0") (pin "12") (pinfunction "~{CBR}_12") (pintype "bidirectional"))
      (node (ref "U4") (pin "11") (pinfunction "I_11") (pintype "input"))
    )
    (net (code "278") (name "~{BCSX}") (class "Default")
      (node (ref "PC0") (pin "9") (pinfunction "~{CSX}_9") (pintype "bidirectional"))
      (node (ref "U1") (pin "4") (pinfunction "G2A_4") (pintype "input"))
      (node (ref "U2") (pin "5") (pinfunction "G2B_5") (pintype "input"))
    )
    (net (code "279") (name "~{BFETCH}") (class "Default")
      (node (ref "PC0") (pin "19") (pinfunction "~{FETCH}_19") (pintype "bidirectional"))
      (node (ref "U8") (pin "14") (pinfunction "Y3_14") (pintype "tri_state"))
    )
    (net (code "280") (name "~{BHALT}") (class "Default")
      (node (ref "PC0") (pin "17") (pinfunction "~{HALT}_17") (pintype "bidirectional"))
      (node (ref "U8") (pin "5") (pinfunction "Y3_5") (pintype "tri_state"))
    )
    (net (code "281") (name "~{BINH}") (class "Default")
      (node (ref "PC0") (pin "11") (pinfunction "~{INH}_11") (pintype "bidirectional"))
      (node (ref "U17") (pin "11") (pinfunction "O_11") (pintype "output"))
    )
    (net (code "282") (name "~{BINT}") (class "Default")
      (node (ref "PC0") (pin "51") (pinfunction "~{INT}_51") (pintype "bidirectional"))
      (node (ref "U18") (pin "10") (pinfunction "I1_10") (pintype "input"))
    )
    (net (code "283") (name "~{BIOSEL}") (class "Default")
      (node (ref "PC0") (pin "16") (pinfunction "~{IOSEL}_16") (pintype "bidirectional"))
      (node (ref "U25") (pin "18") (pinfunction "Y1_18") (pintype "tri_state"))
    )
    (net (code "284") (name "~{BIRQ0}") (class "Default")
      (node (ref "PC0") (pin "53") (pinfunction "~{IRQ0}_53") (pintype "bidirectional"))
      (node (ref "U27") (pin "2") (pinfunction "I1_2") (pintype "input"))
    )
    (net (code "285") (name "~{BIRQ1}") (class "Default")
      (node (ref "PC0") (pin "54") (pinfunction "~{IRQ1}_54") (pintype "bidirectional"))
      (node (ref "U27") (pin "5") (pinfunction "I1_5") (pintype "input"))
    )
    (net (code "286") (name "~{BIRQ2}") (class "Default")
      (node (ref "PC0") (pin "55") (pinfunction "~{IRQ2}_55") (pintype "bidirectional"))
      (node (ref "U27") (pin "13") (pinfunction "I1_13") (pintype "input"))
    )
    (net (code "287") (name "~{BIRQ3}") (class "Default")
      (node (ref "PC0") (pin "56") (pinfunction "~{IRQ3}_56") (pintype "bidirectional"))
      (node (ref "U27") (pin "10") (pinfunction "I1_10") (pintype "input"))
    )
    (net (code "288") (name "~{BIRQ4}") (class "Default")
      (node (ref "PC0") (pin "57") (pinfunction "~{IRQ4}_57") (pintype "bidirectional"))
      (node (ref "U28") (pin "5") (pinfunction "I1_5") (pintype "input"))
    )
    (net (code "289") (name "~{BIRQ5}") (class "Default")
      (node (ref "PC0") (pin "58") (pinfunction "~{IRQ5}_58") (pintype "bidirectional"))
      (node (ref "U28") (pin "2") (pinfunction "I1_2") (pintype "input"))
    )
    (net (code "290") (name "~{BIRQ6}") (class "Default")
      (node (ref "PC0") (pin "59") (pinfunction "~{IRQ6}_59") (pintype "bidirectional"))
      (node (ref "U28") (pin "13") (pinfunction "I1_13") (pintype "input"))
    )
    (net (code "291") (name "~{BIRQ7}") (class "Default")
      (node (ref "PC0") (pin "60") (pinfunction "~{IRQ7}_60") (pintype "bidirectional"))
      (node (ref "U28") (pin "10") (pinfunction "I1_10") (pintype "input"))
    )
    (net (code "292") (name "~{BIRQX}") (class "Default")
      (node (ref "PC0") (pin "52") (pinfunction "~{IRQX}_52") (pintype "bidirectional"))
      (node (ref "U10") (pin "8") (pinfunction "~{Q}_8") (pintype "output"))
    )
    (net (code "293") (name "~{BNMI}") (class "Default")
      (node (ref "JP5") (pin "1") (pinfunction "1_1") (pintype "passive"))
      (node (ref "PC0") (pin "61") (pinfunction "~{NMI}_61") (pintype "bidirectional"))
    )
    (net (code "294") (name "~{BRD}") (class "Default")
      (node (ref "PC0") (pin "21") (pinfunction "~{RD}_21") (pintype "bidirectional"))
      (node (ref "U1") (pin "5") (pinfunction "G2B_5") (pintype "input"))
      (node (ref "U2") (pin "2") (pinfunction "B_2") (pintype "input"))
      (node (ref "U8") (pin "18") (pinfunction "Y1_18") (pintype "tri_state"))
    )
    (net (code "295") (name "~{BRST}") (class "Default")
      (node (ref "PC0") (pin "14") (pinfunction "~{RST}_14") (pintype "bidirectional"))
      (node (ref "U31") (pin "1") (pinfunction "I_1") (pintype "input"))
    )
    (net (code "296") (name "~{BUSACK}") (class "Default")
      (node (ref "U10") (pin "10") (pinfunction "PRE_10") (pintype "input"))
      (node (ref "U8") (pin "13") (pinfunction "A2_13") (pintype "input"))
      (node (ref "U9") (pin "10") (pinfunction "PRE_10") (pintype "input"))
      (node (ref "U9") (pin "6") (pinfunction "~{Q}_6") (pintype "output"))
    )
    (net (code "297") (name "~{BWAIT}") (class "Default")
      (node (ref "PC0") (pin "18") (pinfunction "~{WAIT}_18") (pintype "bidirectional"))
      (node (ref "U31") (pin "13") (pinfunction "I_13") (pintype "input"))
    )
    (net (code "298") (name "~{BWR}") (class "Default")
      (node (ref "PC0") (pin "22") (pinfunction "~{WR}_22") (pintype "bidirectional"))
      (node (ref "U2") (pin "3") (pinfunction "C_3") (pintype "input"))
      (node (ref "U8") (pin "16") (pinfunction "Y2_16") (pintype "tri_state"))
    )
    (net (code "299") (name "~{CS0_READ}") (class "Default")
      (node (ref "U12") (pin "1") (pinfunction "G_1") (pintype "input"))
      (node (ref "U12") (pin "19") (pinfunction "G_19") (pintype "input"))
      (node (ref "U2") (pin "11") (pinfunction "Y4_11") (pintype "output"))
    )
    (net (code "300") (name "~{CS0_WRITE}") (class "Default")
      (node (ref "U10") (pin "3") (pinfunction "CLK_3") (pintype "input"))
      (node (ref "U11") (pin "11") (pinfunction "CLK_11") (pintype "input"))
      (node (ref "U2") (pin "13") (pinfunction "Y2_13") (pintype "output"))
    )
    (net (code "301") (name "~{CS1_READ}") (class "Default")
      (node (ref "U2") (pin "10") (pinfunction "Y5_10") (pintype "output"))
      (node (ref "U21") (pin "1") (pinfunction "G_1") (pintype "input"))
      (node (ref "U21") (pin "19") (pinfunction "G_19") (pintype "input"))
    )
    (net (code "302") (name "~{CS1_WRITE}") (class "Default")
      (node (ref "U2") (pin "12") (pinfunction "Y3_12") (pintype "output"))
      (node (ref "U26") (pin "11") (pinfunction "CLK_11") (pintype "input"))
    )
    (net (code "303") (name "~{HALT}") (class "Default")
      (node (ref "R2") (pin "1") (pinfunction "1_1") (pintype "passive"))
      (node (ref "U17") (pin "8") (pinfunction "O_8") (pintype "output"))
      (node (ref "U8") (pin "15") (pinfunction "A3_15") (pintype "input"))
    )
    (net (code "304") (name "~{IOSEL}") (class "Default")
      (node (ref "U25") (pin "2") (pinfunction "A1_2") (pintype "input"))
      (node (ref "U6") (pin "19") (pinfunction "P=Q_19") (pintype "output"))
    )
    (net (code "305") (name "~{IVP}") (class "Default")
      (node (ref "U16") (pin "1") (pinfunction "OC_1") (pintype "input"))
      (node (ref "U18") (pin "4") (pinfunction "I0_4") (pintype "input"))
      (node (ref "U22") (pin "9") (pinfunction "Y6_9") (pintype "output"))
    )
    (net (code "306") (name "~{MLB}") (class "Default")
      (node (ref "U18") (pin "2") (pinfunction "I1_2") (pintype "input"))
      (node (ref "U20") (pin "5") (pinfunction "~{MLB}_5") (pintype "output"))
    )
    (net (code "307") (name "~{RD}") (class "Default")
      (node (ref "U17") (pin "3") (pinfunction "O_3") (pintype "output"))
      (node (ref "U22") (pin "5") (pinfunction "G2B_5") (pintype "input"))
      (node (ref "U8") (pin "2") (pinfunction "A1_2") (pintype "input"))
    )
    (net (code "308") (name "~{RST}") (class "Default")
      (node (ref "U10") (pin "4") (pinfunction "PRE_4") (pintype "input"))
      (node (ref "U11") (pin "1") (pinfunction "CLR_1") (pintype "input"))
      (node (ref "U18") (pin "5") (pinfunction "I1_5") (pintype "input"))
      (node (ref "U20") (pin "40") (pinfunction "~{RESB}_40") (pintype "input"))
      (node (ref "U26") (pin "1") (pinfunction "CLR_1") (pintype "input"))
      (node (ref "U31") (pin "4") (pinfunction "O_4") (pintype "output"))
      (node (ref "U9") (pin "1") (pinfunction "CLR_1") (pintype "input"))
      (node (ref "U9") (pin "13") (pinfunction "CLR_13") (pintype "input"))
    )
    (net (code "309") (name "~{VINT}") (class "Default")
      (node (ref "U18") (pin "9") (pinfunction "I0_9") (pintype "input"))
      (node (ref "U23") (pin "14") (pinfunction "GS_14") (pintype "output"))
    )
    (net (code "310") (name "~{VPB}") (class "Default")
      (node (ref "JP3") (pin "2") (pinfunction "2_2") (pintype "passive"))
      (node (ref "U19") (pin "5") (pinfunction "I_5") (pintype "input"))
      (node (ref "U20") (pin "1") (pinfunction "~{VPB}_1") (pintype "output"))
      (node (ref "U22") (pin "4") (pinfunction "G2A_4") (pintype "input"))
    )
    (net (code "311") (name "~{WAIT_DMA}") (class "Default")
      (node (ref "R7") (pin "2") (pinfunction "2_2") (pintype "passive"))
      (node (ref "U17") (pin "9") (pinfunction "I0_9") (pintype "input"))
      (node (ref "U9") (pin "8") (pinfunction "~{Q}_8") (pintype "output"))
    )
    (net (code "312") (name "~{WR}") (class "Default")
      (node (ref "U17") (pin "6") (pinfunction "O_6") (pintype "output"))
      (node (ref "U8") (pin "4") (pinfunction "A2_4") (pintype "input"))
    )
  )
)
